# 3dofboard.net
KiCad netlist of a schematic drawn in EAGLE
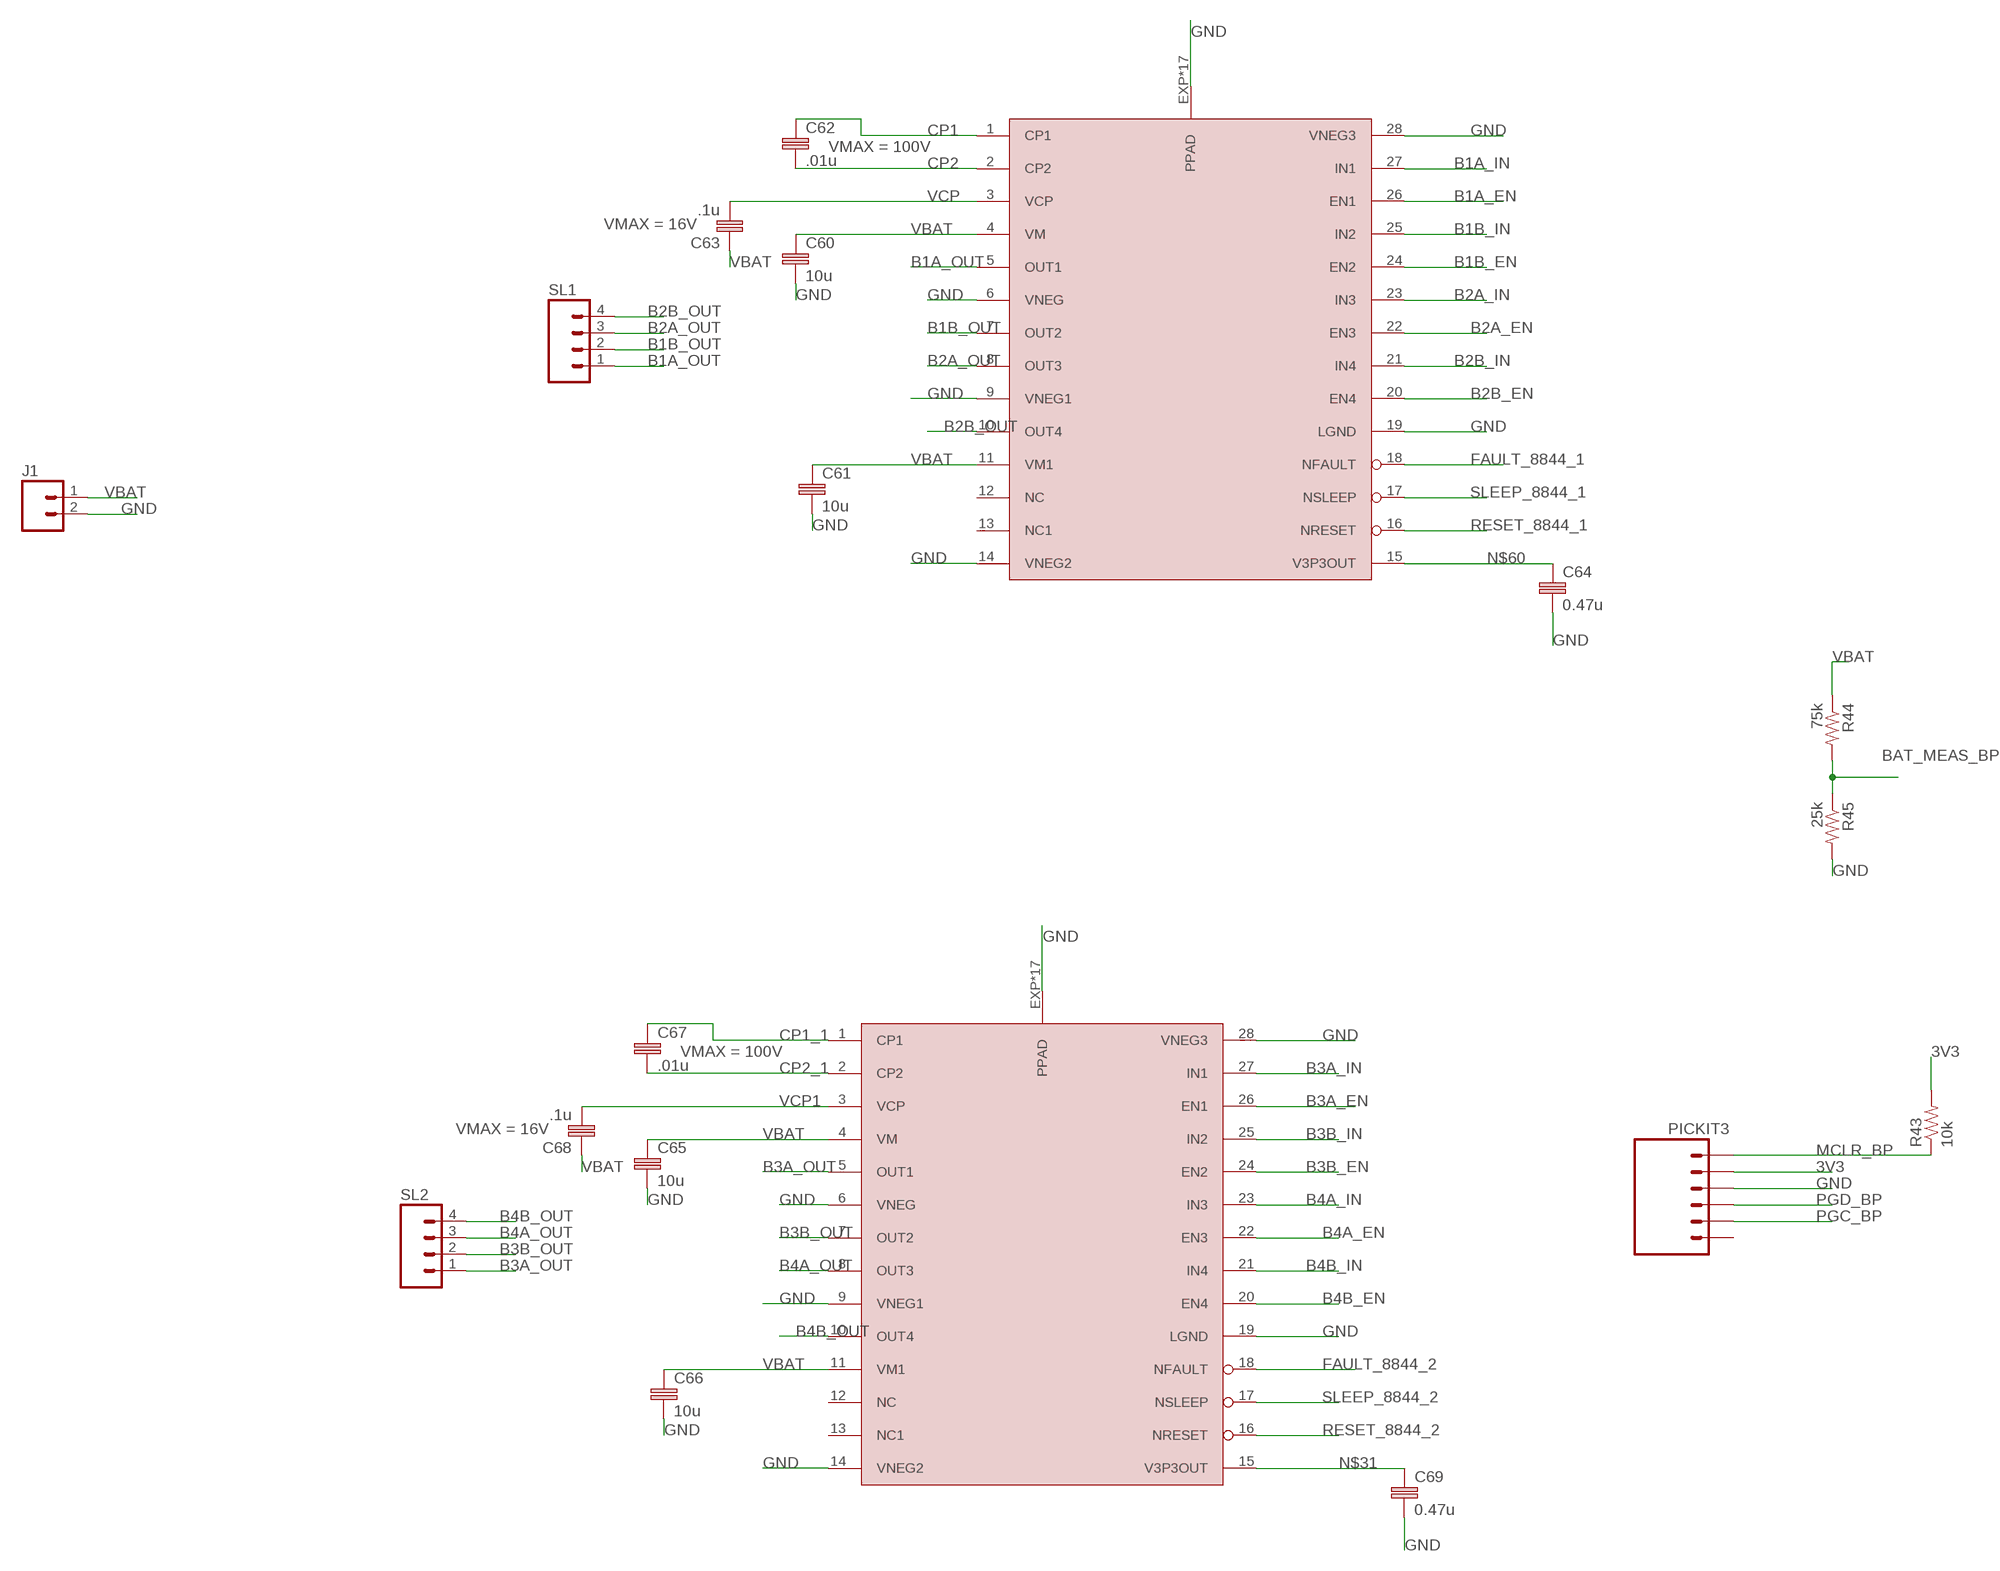
[diagram p0: schematic, sheet 1, part 1 of 3]
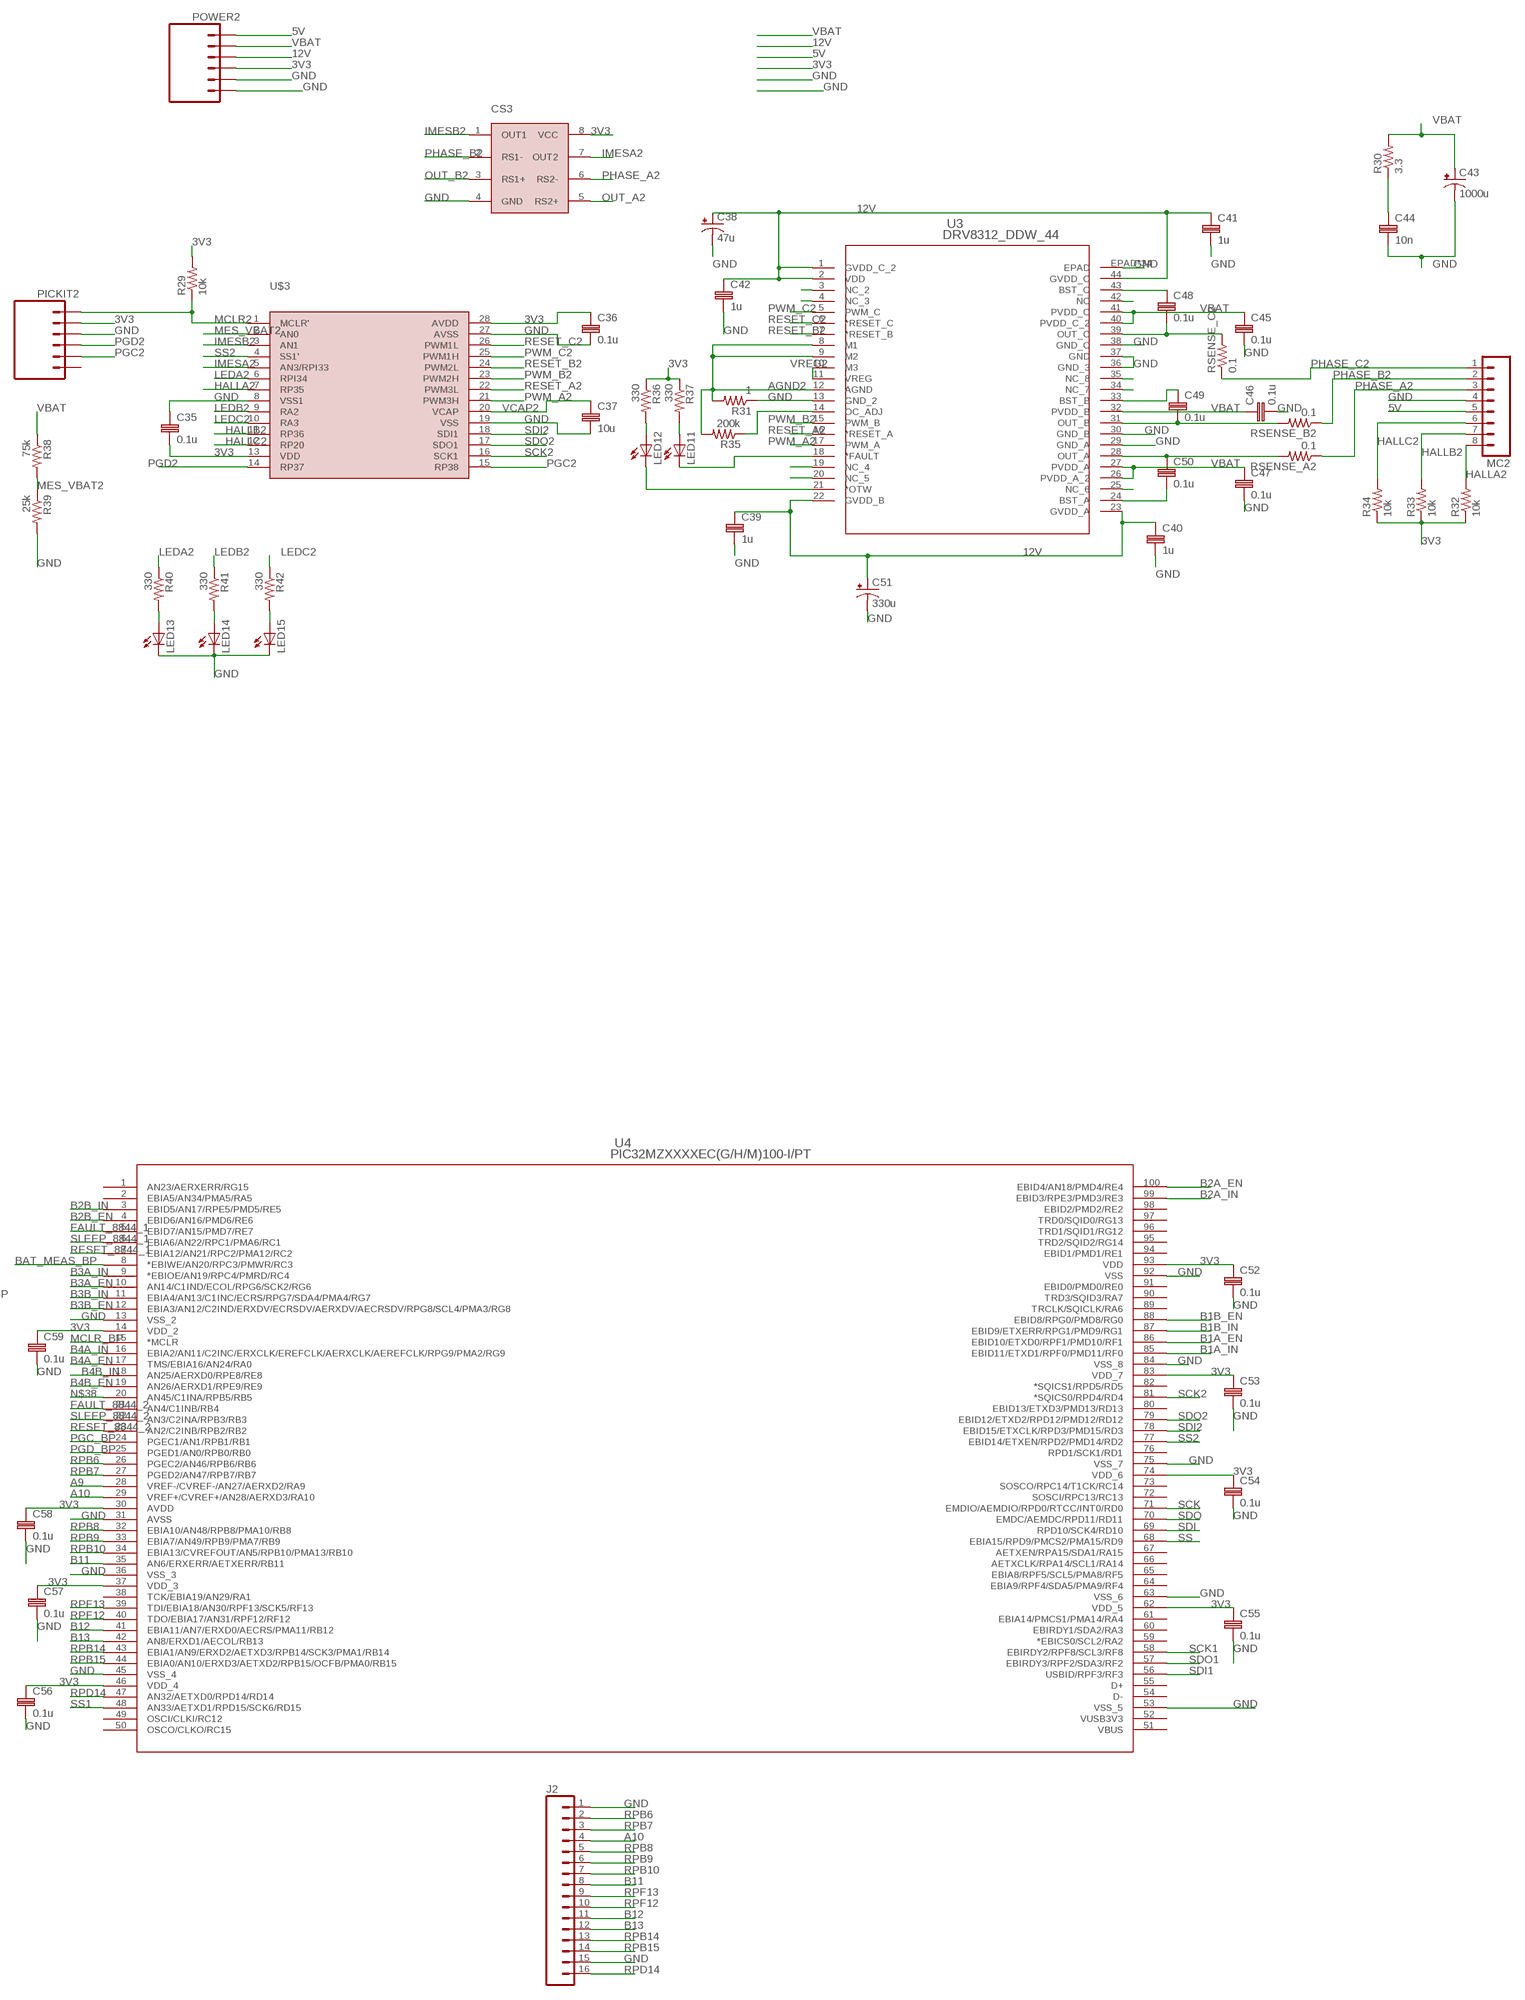
[diagram p1: schematic, sheet 1, part 2 of 3]
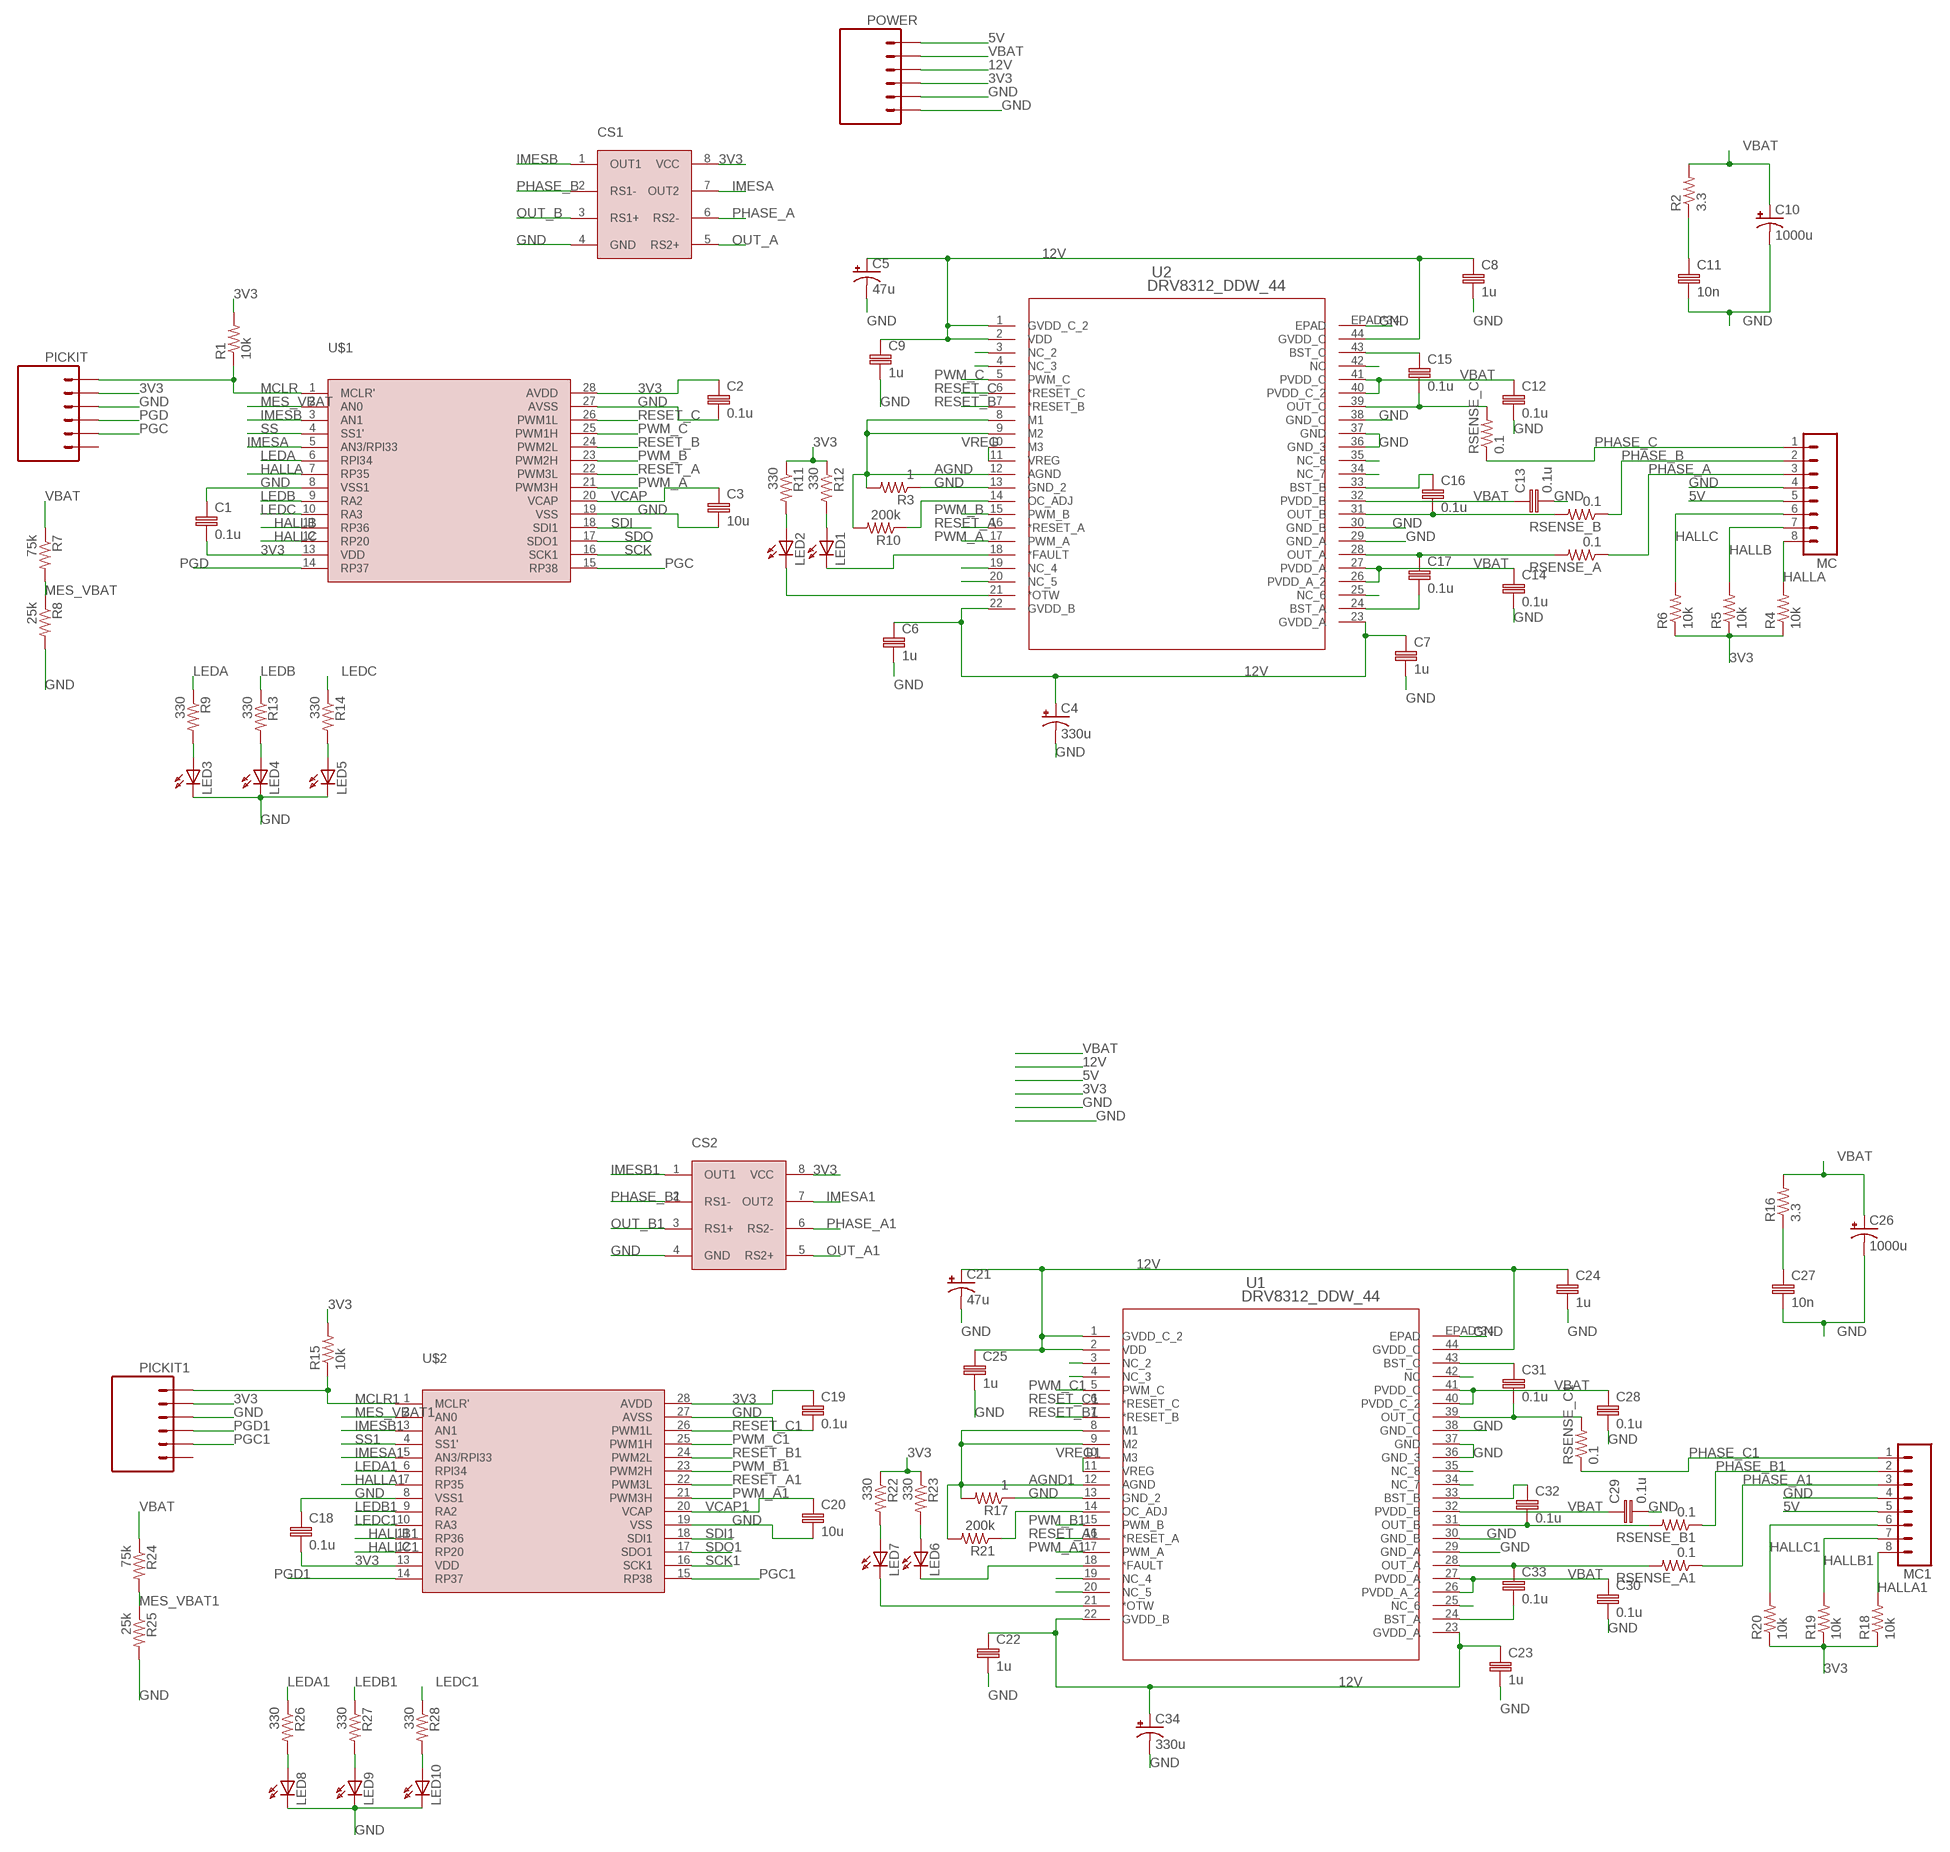
[diagram p2: schematic, sheet 1, part 3 of 3]

(export (version "E")
  (design (tool "Eeschema 10.0.6"))
  (components
    (comp (ref "C1")
      (value "0.1u")
      (footprint "eagle-import:0805")
      (libsource (lib "eagle-import") (part "CAP0805"))
    )
    (comp (ref "C2")
      (value "0.1u")
      (footprint "eagle-import:0805")
      (libsource (lib "eagle-import") (part "CAP0805"))
    )
    (comp (ref "C3")
      (value "10u")
      (footprint "eagle-import:0805")
      (libsource (lib "eagle-import") (part "CAP0805"))
    )
    (comp (ref "C4")
      (value "330u")
      (footprint "eagle-import:E3,5-8")
      (libsource (lib "eagle-import") (part "CPOL-USE3.5-8"))
    )
    (comp (ref "C5")
      (value "47u")
      (footprint "eagle-import:CPOL-RADIAL-100UF-25V")
      (libsource (lib "eagle-import") (part "CAP_POLPTH1"))
    )
    (comp (ref "C6")
      (value "1u")
      (footprint "eagle-import:0805")
      (libsource (lib "eagle-import") (part "CAP0805"))
    )
    (comp (ref "C7")
      (value "1u")
      (footprint "eagle-import:0805")
      (libsource (lib "eagle-import") (part "CAP0805"))
    )
    (comp (ref "C8")
      (value "1u")
      (footprint "eagle-import:0805")
      (libsource (lib "eagle-import") (part "CAP0805"))
    )
    (comp (ref "C9")
      (value "1u")
      (footprint "eagle-import:0805")
      (libsource (lib "eagle-import") (part "CAP0805"))
    )
    (comp (ref "C10")
      (value "1000u")
      (footprint "eagle-import:CPOL-RADIAL-1000UF-25V")
      (libsource (lib "eagle-import") (part "CAP_POLPTH4"))
    )
    (comp (ref "C11")
      (value "10n")
      (footprint "eagle-import:0805")
      (libsource (lib "eagle-import") (part "CAP0805"))
    )
    (comp (ref "C12")
      (value "0.1u")
      (footprint "eagle-import:0805")
      (libsource (lib "eagle-import") (part "CAP0805"))
    )
    (comp (ref "C13")
      (value "0.1u")
      (footprint "eagle-import:0805")
      (libsource (lib "eagle-import") (part "CAP0805"))
    )
    (comp (ref "C14")
      (value "0.1u")
      (footprint "eagle-import:0805")
      (libsource (lib "eagle-import") (part "CAP0805"))
    )
    (comp (ref "C15")
      (value "0.1u")
      (footprint "eagle-import:0805")
      (libsource (lib "eagle-import") (part "CAP0805"))
    )
    (comp (ref "C16")
      (value "0.1u")
      (footprint "eagle-import:0805")
      (libsource (lib "eagle-import") (part "CAP0805"))
    )
    (comp (ref "C17")
      (value "0.1u")
      (footprint "eagle-import:0805")
      (libsource (lib "eagle-import") (part "CAP0805"))
    )
    (comp (ref "C18")
      (value "0.1u")
      (footprint "eagle-import:0805")
      (libsource (lib "eagle-import") (part "CAP0805"))
    )
    (comp (ref "C19")
      (value "0.1u")
      (footprint "eagle-import:0805")
      (libsource (lib "eagle-import") (part "CAP0805"))
    )
    (comp (ref "C20")
      (value "10u")
      (footprint "eagle-import:0805")
      (libsource (lib "eagle-import") (part "CAP0805"))
    )
    (comp (ref "C21")
      (value "47u")
      (footprint "eagle-import:CPOL-RADIAL-100UF-25V")
      (libsource (lib "eagle-import") (part "CAP_POLPTH1"))
    )
    (comp (ref "C22")
      (value "1u")
      (footprint "eagle-import:0805")
      (libsource (lib "eagle-import") (part "CAP0805"))
    )
    (comp (ref "C23")
      (value "1u")
      (footprint "eagle-import:0805")
      (libsource (lib "eagle-import") (part "CAP0805"))
    )
    (comp (ref "C24")
      (value "1u")
      (footprint "eagle-import:0805")
      (libsource (lib "eagle-import") (part "CAP0805"))
    )
    (comp (ref "C25")
      (value "1u")
      (footprint "eagle-import:0805")
      (libsource (lib "eagle-import") (part "CAP0805"))
    )
    (comp (ref "C26")
      (value "1000u")
      (footprint "eagle-import:CPOL-RADIAL-1000UF-25V")
      (libsource (lib "eagle-import") (part "CAP_POLPTH4"))
    )
    (comp (ref "C27")
      (value "10n")
      (footprint "eagle-import:0805")
      (libsource (lib "eagle-import") (part "CAP0805"))
    )
    (comp (ref "C28")
      (value "0.1u")
      (footprint "eagle-import:0805")
      (libsource (lib "eagle-import") (part "CAP0805"))
    )
    (comp (ref "C29")
      (value "0.1u")
      (footprint "eagle-import:0805")
      (libsource (lib "eagle-import") (part "CAP0805"))
    )
    (comp (ref "C30")
      (value "0.1u")
      (footprint "eagle-import:0805")
      (libsource (lib "eagle-import") (part "CAP0805"))
    )
    (comp (ref "C31")
      (value "0.1u")
      (footprint "eagle-import:0805")
      (libsource (lib "eagle-import") (part "CAP0805"))
    )
    (comp (ref "C32")
      (value "0.1u")
      (footprint "eagle-import:0805")
      (libsource (lib "eagle-import") (part "CAP0805"))
    )
    (comp (ref "C33")
      (value "0.1u")
      (footprint "eagle-import:0805")
      (libsource (lib "eagle-import") (part "CAP0805"))
    )
    (comp (ref "C34")
      (value "330u")
      (footprint "eagle-import:E3,5-8")
      (libsource (lib "eagle-import") (part "CPOL-USE3.5-8"))
    )
    (comp (ref "C35")
      (value "0.1u")
      (footprint "eagle-import:0805")
      (libsource (lib "eagle-import") (part "CAP0805"))
    )
    (comp (ref "C36")
      (value "0.1u")
      (footprint "eagle-import:0805")
      (libsource (lib "eagle-import") (part "CAP0805"))
    )
    (comp (ref "C37")
      (value "10u")
      (footprint "eagle-import:0805")
      (libsource (lib "eagle-import") (part "CAP0805"))
    )
    (comp (ref "C38")
      (value "47u")
      (footprint "eagle-import:CPOL-RADIAL-100UF-25V")
      (libsource (lib "eagle-import") (part "CAP_POLPTH1"))
    )
    (comp (ref "C39")
      (value "1u")
      (footprint "eagle-import:0805")
      (libsource (lib "eagle-import") (part "CAP0805"))
    )
    (comp (ref "C40")
      (value "1u")
      (footprint "eagle-import:0805")
      (libsource (lib "eagle-import") (part "CAP0805"))
    )
    (comp (ref "C41")
      (value "1u")
      (footprint "eagle-import:0805")
      (libsource (lib "eagle-import") (part "CAP0805"))
    )
    (comp (ref "C42")
      (value "1u")
      (footprint "eagle-import:0805")
      (libsource (lib "eagle-import") (part "CAP0805"))
    )
    (comp (ref "C43")
      (value "1000u")
      (footprint "eagle-import:CPOL-RADIAL-1000UF-25V")
      (libsource (lib "eagle-import") (part "CAP_POLPTH4"))
    )
    (comp (ref "C44")
      (value "10n")
      (footprint "eagle-import:0805")
      (libsource (lib "eagle-import") (part "CAP0805"))
    )
    (comp (ref "C45")
      (value "0.1u")
      (footprint "eagle-import:0805")
      (libsource (lib "eagle-import") (part "CAP0805"))
    )
    (comp (ref "C46")
      (value "0.1u")
      (footprint "eagle-import:0805")
      (libsource (lib "eagle-import") (part "CAP0805"))
    )
    (comp (ref "C47")
      (value "0.1u")
      (footprint "eagle-import:0805")
      (libsource (lib "eagle-import") (part "CAP0805"))
    )
    (comp (ref "C48")
      (value "0.1u")
      (footprint "eagle-import:0805")
      (libsource (lib "eagle-import") (part "CAP0805"))
    )
    (comp (ref "C49")
      (value "0.1u")
      (footprint "eagle-import:0805")
      (libsource (lib "eagle-import") (part "CAP0805"))
    )
    (comp (ref "C50")
      (value "0.1u")
      (footprint "eagle-import:0805")
      (libsource (lib "eagle-import") (part "CAP0805"))
    )
    (comp (ref "C51")
      (value "330u")
      (footprint "eagle-import:E3,5-8")
      (libsource (lib "eagle-import") (part "CPOL-USE3.5-8"))
    )
    (comp (ref "C52")
      (value "0.1u")
      (footprint "eagle-import:0805")
      (libsource (lib "eagle-import") (part "CAP0805"))
    )
    (comp (ref "C53")
      (value "0.1u")
      (footprint "eagle-import:0805")
      (libsource (lib "eagle-import") (part "CAP0805"))
    )
    (comp (ref "C54")
      (value "0.1u")
      (footprint "eagle-import:0805")
      (libsource (lib "eagle-import") (part "CAP0805"))
    )
    (comp (ref "C55")
      (value "0.1u")
      (footprint "eagle-import:0805")
      (libsource (lib "eagle-import") (part "CAP0805"))
    )
    (comp (ref "C56")
      (value "0.1u")
      (footprint "eagle-import:0805")
      (libsource (lib "eagle-import") (part "CAP0805"))
    )
    (comp (ref "C57")
      (value "0.1u")
      (footprint "eagle-import:0805")
      (libsource (lib "eagle-import") (part "CAP0805"))
    )
    (comp (ref "C58")
      (value "0.1u")
      (footprint "eagle-import:0805")
      (libsource (lib "eagle-import") (part "CAP0805"))
    )
    (comp (ref "C59")
      (value "0.1u")
      (footprint "eagle-import:0805")
      (libsource (lib "eagle-import") (part "CAP0805"))
    )
    (comp (ref "C60")
      (value "10u")
      (footprint "eagle-import:0805")
      (libsource (lib "eagle-import") (part "CAP0805"))
    )
    (comp (ref "C61")
      (value "10u")
      (footprint "eagle-import:0805")
      (libsource (lib "eagle-import") (part "CAP0805"))
    )
    (comp (ref "C62")
      (value ".01u")
      (footprint "eagle-import:0805")
      (fields (field (name "VMAX") "100V"))
      (libsource (lib "eagle-import") (part "CAP0805"))
    )
    (comp (ref "C63")
      (value ".1u")
      (footprint "eagle-import:0805")
      (fields (field (name "VMAX") "16V"))
      (libsource (lib "eagle-import") (part "CAP0805"))
    )
    (comp (ref "C64")
      (value "0.47u")
      (footprint "eagle-import:0805")
      (libsource (lib "eagle-import") (part "CAP0805"))
    )
    (comp (ref "C65")
      (value "10u")
      (footprint "eagle-import:0805")
      (libsource (lib "eagle-import") (part "CAP0805"))
    )
    (comp (ref "C66")
      (value "10u")
      (footprint "eagle-import:0805")
      (libsource (lib "eagle-import") (part "CAP0805"))
    )
    (comp (ref "C67")
      (value ".01u")
      (footprint "eagle-import:0805")
      (fields (field (name "VMAX") "100V"))
      (libsource (lib "eagle-import") (part "CAP0805"))
    )
    (comp (ref "C68")
      (value ".1u")
      (footprint "eagle-import:0805")
      (fields (field (name "VMAX") "16V"))
      (libsource (lib "eagle-import") (part "CAP0805"))
    )
    (comp (ref "C69")
      (value "0.47u")
      (footprint "eagle-import:0805")
      (libsource (lib "eagle-import") (part "CAP0805"))
    )
    (comp (ref "CS1")
      (value "MAX4376")
      (footprint "eagle-import:SO8")
      (libsource (lib "eagle-import") (part "MAX4376"))
    )
    (comp (ref "CS2")
      (value "MAX4376")
      (footprint "eagle-import:SO8")
      (libsource (lib "eagle-import") (part "MAX4376"))
    )
    (comp (ref "CS3")
      (value "MAX4376")
      (footprint "eagle-import:SO8")
      (libsource (lib "eagle-import") (part "MAX4376"))
    )
    (comp (ref "J1")
      (value "M02LOCK")
      (footprint "eagle-import:1X02_LOCK")
      (libsource (lib "eagle-import") (part "M02LOCK"))
    )
    (comp (ref "J2")
      (value "M16DUAL_ROW")
      (footprint "eagle-import:2X8")
      (libsource (lib "eagle-import") (part "M16DUAL_ROW"))
    )
    (comp (ref "LED1")
      (value "LED0805")
      (footprint "eagle-import:LED-0805")
      (libsource (lib "eagle-import") (part "LED0805"))
    )
    (comp (ref "LED2")
      (value "LED0805")
      (footprint "eagle-import:LED-0805")
      (libsource (lib "eagle-import") (part "LED0805"))
    )
    (comp (ref "LED3")
      (value "LED0805")
      (footprint "eagle-import:LED-0805")
      (libsource (lib "eagle-import") (part "LED0805"))
    )
    (comp (ref "LED4")
      (value "LED0805")
      (footprint "eagle-import:LED-0805")
      (libsource (lib "eagle-import") (part "LED0805"))
    )
    (comp (ref "LED5")
      (value "LED0805")
      (footprint "eagle-import:LED-0805")
      (libsource (lib "eagle-import") (part "LED0805"))
    )
    (comp (ref "LED6")
      (value "LED0805")
      (footprint "eagle-import:LED-0805")
      (libsource (lib "eagle-import") (part "LED0805"))
    )
    (comp (ref "LED7")
      (value "LED0805")
      (footprint "eagle-import:LED-0805")
      (libsource (lib "eagle-import") (part "LED0805"))
    )
    (comp (ref "LED8")
      (value "LED0805")
      (footprint "eagle-import:LED-0805")
      (libsource (lib "eagle-import") (part "LED0805"))
    )
    (comp (ref "LED9")
      (value "LED0805")
      (footprint "eagle-import:LED-0805")
      (libsource (lib "eagle-import") (part "LED0805"))
    )
    (comp (ref "LED10")
      (value "LED0805")
      (footprint "eagle-import:LED-0805")
      (libsource (lib "eagle-import") (part "LED0805"))
    )
    (comp (ref "LED11")
      (value "LED0805")
      (footprint "eagle-import:LED-0805")
      (libsource (lib "eagle-import") (part "LED0805"))
    )
    (comp (ref "LED12")
      (value "LED0805")
      (footprint "eagle-import:LED-0805")
      (libsource (lib "eagle-import") (part "LED0805"))
    )
    (comp (ref "LED13")
      (value "LED0805")
      (footprint "eagle-import:LED-0805")
      (libsource (lib "eagle-import") (part "LED0805"))
    )
    (comp (ref "LED14")
      (value "LED0805")
      (footprint "eagle-import:LED-0805")
      (libsource (lib "eagle-import") (part "LED0805"))
    )
    (comp (ref "LED15")
      (value "LED0805")
      (footprint "eagle-import:LED-0805")
      (libsource (lib "eagle-import") (part "LED0805"))
    )
    (comp (ref "MC")
      (value "M08")
      (footprint "eagle-import:08P")
      (libsource (lib "eagle-import") (part "M08"))
    )
    (comp (ref "MC1")
      (value "M08")
      (footprint "eagle-import:08P")
      (libsource (lib "eagle-import") (part "M08"))
    )
    (comp (ref "MC2")
      (value "M08")
      (footprint "eagle-import:08P")
      (libsource (lib "eagle-import") (part "M08"))
    )
    (comp (ref "PICKIT")
      (value "M06LOCK")
      (footprint "eagle-import:1X06_LOCK")
      (libsource (lib "eagle-import") (part "M06LOCK"))
    )
    (comp (ref "PICKIT1")
      (value "M06LOCK")
      (footprint "eagle-import:1X06_LOCK")
      (libsource (lib "eagle-import") (part "M06LOCK"))
    )
    (comp (ref "PICKIT2")
      (value "M06LOCK")
      (footprint "eagle-import:1X06_LOCK")
      (libsource (lib "eagle-import") (part "M06LOCK"))
    )
    (comp (ref "PICKIT3")
      (value "M06LOCK")
      (footprint "eagle-import:1X06_LOCK")
      (libsource (lib "eagle-import") (part "M06LOCK"))
    )
    (comp (ref "POWER")
      (value "M06LOCK")
      (footprint "eagle-import:1X06_LOCK")
      (libsource (lib "eagle-import") (part "M06LOCK"))
    )
    (comp (ref "POWER2")
      (value "M06LOCK")
      (footprint "eagle-import:1X06_LOCK")
      (libsource (lib "eagle-import") (part "M06LOCK"))
    )
    (comp (ref "R1")
      (value "10k")
      (footprint "eagle-import:0805")
      (libsource (lib "eagle-import") (part "RESISTOR0805-RES"))
    )
    (comp (ref "R2")
      (value "3.3")
      (footprint "eagle-import:0805")
      (libsource (lib "eagle-import") (part "RESISTOR0805-RES"))
    )
    (comp (ref "R3")
      (value "1")
      (footprint "eagle-import:0805")
      (libsource (lib "eagle-import") (part "RESISTOR0805-RES"))
    )
    (comp (ref "R4")
      (value "10k")
      (footprint "eagle-import:0805")
      (libsource (lib "eagle-import") (part "RESISTOR0805-RES"))
    )
    (comp (ref "R5")
      (value "10k")
      (footprint "eagle-import:0805")
      (libsource (lib "eagle-import") (part "RESISTOR0805-RES"))
    )
    (comp (ref "R6")
      (value "10k")
      (footprint "eagle-import:0805")
      (libsource (lib "eagle-import") (part "RESISTOR0805-RES"))
    )
    (comp (ref "R7")
      (value "75k")
      (footprint "eagle-import:0805")
      (libsource (lib "eagle-import") (part "RESISTOR0805-RES"))
    )
    (comp (ref "R8")
      (value "25k")
      (footprint "eagle-import:0805")
      (libsource (lib "eagle-import") (part "RESISTOR0805-RES"))
    )
    (comp (ref "R9")
      (value "330")
      (footprint "eagle-import:0805")
      (libsource (lib "eagle-import") (part "RESISTOR0805-RES"))
    )
    (comp (ref "R10")
      (value "200k")
      (footprint "eagle-import:0805")
      (libsource (lib "eagle-import") (part "RESISTOR0805-RES"))
    )
    (comp (ref "R11")
      (value "330")
      (footprint "eagle-import:0805")
      (libsource (lib "eagle-import") (part "RESISTOR0805-RES"))
    )
    (comp (ref "R12")
      (value "330")
      (footprint "eagle-import:0805")
      (libsource (lib "eagle-import") (part "RESISTOR0805-RES"))
    )
    (comp (ref "R13")
      (value "330")
      (footprint "eagle-import:0805")
      (libsource (lib "eagle-import") (part "RESISTOR0805-RES"))
    )
    (comp (ref "R14")
      (value "330")
      (footprint "eagle-import:0805")
      (libsource (lib "eagle-import") (part "RESISTOR0805-RES"))
    )
    (comp (ref "R15")
      (value "10k")
      (footprint "eagle-import:0805")
      (libsource (lib "eagle-import") (part "RESISTOR0805-RES"))
    )
    (comp (ref "R16")
      (value "3.3")
      (footprint "eagle-import:0805")
      (libsource (lib "eagle-import") (part "RESISTOR0805-RES"))
    )
    (comp (ref "R17")
      (value "1")
      (footprint "eagle-import:0805")
      (libsource (lib "eagle-import") (part "RESISTOR0805-RES"))
    )
    (comp (ref "R18")
      (value "10k")
      (footprint "eagle-import:0805")
      (libsource (lib "eagle-import") (part "RESISTOR0805-RES"))
    )
    (comp (ref "R19")
      (value "10k")
      (footprint "eagle-import:0805")
      (libsource (lib "eagle-import") (part "RESISTOR0805-RES"))
    )
    (comp (ref "R20")
      (value "10k")
      (footprint "eagle-import:0805")
      (libsource (lib "eagle-import") (part "RESISTOR0805-RES"))
    )
    (comp (ref "R21")
      (value "200k")
      (footprint "eagle-import:0805")
      (libsource (lib "eagle-import") (part "RESISTOR0805-RES"))
    )
    (comp (ref "R22")
      (value "330")
      (footprint "eagle-import:0805")
      (libsource (lib "eagle-import") (part "RESISTOR0805-RES"))
    )
    (comp (ref "R23")
      (value "330")
      (footprint "eagle-import:0805")
      (libsource (lib "eagle-import") (part "RESISTOR0805-RES"))
    )
    (comp (ref "R24")
      (value "75k")
      (footprint "eagle-import:0805")
      (libsource (lib "eagle-import") (part "RESISTOR0805-RES"))
    )
    (comp (ref "R25")
      (value "25k")
      (footprint "eagle-import:0805")
      (libsource (lib "eagle-import") (part "RESISTOR0805-RES"))
    )
    (comp (ref "R26")
      (value "330")
      (footprint "eagle-import:0805")
      (libsource (lib "eagle-import") (part "RESISTOR0805-RES"))
    )
    (comp (ref "R27")
      (value "330")
      (footprint "eagle-import:0805")
      (libsource (lib "eagle-import") (part "RESISTOR0805-RES"))
    )
    (comp (ref "R28")
      (value "330")
      (footprint "eagle-import:0805")
      (libsource (lib "eagle-import") (part "RESISTOR0805-RES"))
    )
    (comp (ref "R29")
      (value "10k")
      (footprint "eagle-import:0805")
      (libsource (lib "eagle-import") (part "RESISTOR0805-RES"))
    )
    (comp (ref "R30")
      (value "3.3")
      (footprint "eagle-import:0805")
      (libsource (lib "eagle-import") (part "RESISTOR0805-RES"))
    )
    (comp (ref "R31")
      (value "1")
      (footprint "eagle-import:0805")
      (libsource (lib "eagle-import") (part "RESISTOR0805-RES"))
    )
    (comp (ref "R32")
      (value "10k")
      (footprint "eagle-import:0805")
      (libsource (lib "eagle-import") (part "RESISTOR0805-RES"))
    )
    (comp (ref "R33")
      (value "10k")
      (footprint "eagle-import:0805")
      (libsource (lib "eagle-import") (part "RESISTOR0805-RES"))
    )
    (comp (ref "R34")
      (value "10k")
      (footprint "eagle-import:0805")
      (libsource (lib "eagle-import") (part "RESISTOR0805-RES"))
    )
    (comp (ref "R35")
      (value "200k")
      (footprint "eagle-import:0805")
      (libsource (lib "eagle-import") (part "RESISTOR0805-RES"))
    )
    (comp (ref "R36")
      (value "330")
      (footprint "eagle-import:0805")
      (libsource (lib "eagle-import") (part "RESISTOR0805-RES"))
    )
    (comp (ref "R37")
      (value "330")
      (footprint "eagle-import:0805")
      (libsource (lib "eagle-import") (part "RESISTOR0805-RES"))
    )
    (comp (ref "R38")
      (value "75k")
      (footprint "eagle-import:0805")
      (libsource (lib "eagle-import") (part "RESISTOR0805-RES"))
    )
    (comp (ref "R39")
      (value "25k")
      (footprint "eagle-import:0805")
      (libsource (lib "eagle-import") (part "RESISTOR0805-RES"))
    )
    (comp (ref "R40")
      (value "330")
      (footprint "eagle-import:0805")
      (libsource (lib "eagle-import") (part "RESISTOR0805-RES"))
    )
    (comp (ref "R41")
      (value "330")
      (footprint "eagle-import:0805")
      (libsource (lib "eagle-import") (part "RESISTOR0805-RES"))
    )
    (comp (ref "R42")
      (value "330")
      (footprint "eagle-import:0805")
      (libsource (lib "eagle-import") (part "RESISTOR0805-RES"))
    )
    (comp (ref "R43")
      (value "10k")
      (footprint "eagle-import:0805")
      (libsource (lib "eagle-import") (part "RESISTOR0805-RES"))
    )
    (comp (ref "R44")
      (value "75k")
      (footprint "eagle-import:0805")
      (libsource (lib "eagle-import") (part "RESISTOR0805-RES"))
    )
    (comp (ref "R45")
      (value "25k")
      (footprint "eagle-import:0805")
      (libsource (lib "eagle-import") (part "RESISTOR0805-RES"))
    )
    (comp (ref "RSENSE_A")
      (value "0.1")
      (footprint "eagle-import:0805")
      (libsource (lib "eagle-import") (part "RESISTOR0805-RES"))
    )
    (comp (ref "RSENSE_A1")
      (value "0.1")
      (footprint "eagle-import:0805")
      (libsource (lib "eagle-import") (part "RESISTOR0805-RES"))
    )
    (comp (ref "RSENSE_A2")
      (value "0.1")
      (footprint "eagle-import:0805")
      (libsource (lib "eagle-import") (part "RESISTOR0805-RES"))
    )
    (comp (ref "RSENSE_B")
      (value "0.1")
      (footprint "eagle-import:0805")
      (libsource (lib "eagle-import") (part "RESISTOR0805-RES"))
    )
    (comp (ref "RSENSE_B1")
      (value "0.1")
      (footprint "eagle-import:0805")
      (libsource (lib "eagle-import") (part "RESISTOR0805-RES"))
    )
    (comp (ref "RSENSE_B2")
      (value "0.1")
      (footprint "eagle-import:0805")
      (libsource (lib "eagle-import") (part "RESISTOR0805-RES"))
    )
    (comp (ref "RSENSE_C")
      (value "0.1")
      (footprint "eagle-import:0805")
      (libsource (lib "eagle-import") (part "RESISTOR0805-RES"))
    )
    (comp (ref "RSENSE_C1")
      (value "0.1")
      (footprint "eagle-import:0805")
      (libsource (lib "eagle-import") (part "RESISTOR0805-RES"))
    )
    (comp (ref "RSENSE_C2")
      (value "0.1")
      (footprint "eagle-import:0805")
      (libsource (lib "eagle-import") (part "RESISTOR0805-RES"))
    )
    (comp (ref "SL1")
      (value "M04LOCK")
      (footprint "eagle-import:1X04_LOCK")
      (libsource (lib "eagle-import") (part "M04LOCK"))
    )
    (comp (ref "SL2")
      (value "M04LOCK")
      (footprint "eagle-import:1X04_LOCK")
      (libsource (lib "eagle-import") (part "M04LOCK"))
    )
    (comp (ref "U$1")
      (value "DSPIC33EP512MC502-28SSOP")
      (footprint "eagle-import:SSOP28")
      (libsource (lib "eagle-import") (part "DSPIC33EP512MC502-28SSOP"))
    )
    (comp (ref "U$2")
      (value "DSPIC33EP512MC502-28SSOP")
      (footprint "eagle-import:SSOP28")
      (libsource (lib "eagle-import") (part "DSPIC33EP512MC502-28SSOP"))
    )
    (comp (ref "U$3")
      (value "DSPIC33EP512MC502-28SSOP")
      (footprint "eagle-import:SSOP28")
      (libsource (lib "eagle-import") (part "DSPIC33EP512MC502-28SSOP"))
    )
    (comp (ref "U$4")
      (value "DRV8844PWP")
      (footprint "eagle-import:TSSOP-28")
      (libsource (lib "eagle-import") (part "DRV8844PWP"))
    )
    (comp (ref "U$5")
      (value "DRV8844PWP")
      (footprint "eagle-import:TSSOP-28")
      (libsource (lib "eagle-import") (part "DRV8844PWP"))
    )
    (comp (ref "U1")
      (value "DRV8312_DDW_44")
      (footprint "eagle-import:DDW44_8P26X4P31")
      (fields
        (field (name "GENERIC_PART_NUMBER") "DRV8312")
        (field (name "MANUFACTURER") "Texas Instruments")
        (field (name "MANUFACTURER_PART_NUMBER") "drv8312_ddw_44")
      )
      (libsource (lib "eagle-import") (part "DRV8312_DDW_44"))
    )
    (comp (ref "U2")
      (value "DRV8312_DDW_44")
      (footprint "eagle-import:DDW44_8P26X4P31")
      (fields
        (field (name "GENERIC_PART_NUMBER") "DRV8312")
        (field (name "MANUFACTURER") "Texas Instruments")
        (field (name "MANUFACTURER_PART_NUMBER") "drv8312_ddw_44")
      )
      (libsource (lib "eagle-import") (part "DRV8312_DDW_44"))
    )
    (comp (ref "U3")
      (value "DRV8312_DDW_44")
      (footprint "eagle-import:DDW44_8P26X4P31")
      (fields
        (field (name "GENERIC_PART_NUMBER") "DRV8312")
        (field (name "MANUFACTURER") "Texas Instruments")
        (field (name "MANUFACTURER_PART_NUMBER") "drv8312_ddw_44")
      )
      (libsource (lib "eagle-import") (part "DRV8312_DDW_44"))
    )
    (comp (ref "U4")
      (value "PIC32MZXXXXEC(G/H/M)100-I/PT")
      (footprint "eagle-import:TQFP100_12X12MC")
      (fields (field (name "MANUFACTURER_PART_NUMBER") "pic32mz1024ecg100-i/pt"))
      (libsource (lib "eagle-import") (part "PIC32MZXXXXEC(G/H/M)100-I/PT"))
    )
  )
  (nets
    (net (code "1") (name "/3V3") (class "Default")
      (node (ref "C1") (pin "2") (pinfunction "2_2") (pintype "passive"))
      (node (ref "C18") (pin "2") (pinfunction "2_2") (pintype "passive"))
      (node (ref "C19") (pin "1") (pinfunction "1_1") (pintype "passive"))
      (node (ref "C2") (pin "1") (pinfunction "1_1") (pintype "passive"))
      (node (ref "C35") (pin "2") (pinfunction "2_2") (pintype "passive"))
      (node (ref "C36") (pin "1") (pinfunction "1_1") (pintype "passive"))
      (node (ref "C52") (pin "1") (pinfunction "1_1") (pintype "passive"))
      (node (ref "C53") (pin "1") (pinfunction "1_1") (pintype "passive"))
      (node (ref "C54") (pin "1") (pinfunction "1_1") (pintype "passive"))
      (node (ref "C55") (pin "1") (pinfunction "1_1") (pintype "passive"))
      (node (ref "C56") (pin "1") (pinfunction "1_1") (pintype "passive"))
      (node (ref "C57") (pin "1") (pinfunction "1_1") (pintype "passive"))
      (node (ref "C58") (pin "1") (pinfunction "1_1") (pintype "passive"))
      (node (ref "C59") (pin "1") (pinfunction "1_1") (pintype "passive"))
      (node (ref "CS1") (pin "8") (pinfunction "VCC_8") (pintype "bidirectional"))
      (node (ref "CS2") (pin "8") (pinfunction "VCC_8") (pintype "bidirectional"))
      (node (ref "CS3") (pin "8") (pinfunction "VCC_8") (pintype "bidirectional"))
      (node (ref "PICKIT") (pin "2") (pinfunction "2_2") (pintype "passive"))
      (node (ref "PICKIT1") (pin "2") (pinfunction "2_2") (pintype "passive"))
      (node (ref "PICKIT2") (pin "2") (pinfunction "2_2") (pintype "passive"))
      (node (ref "PICKIT3") (pin "2") (pinfunction "2_2") (pintype "passive"))
      (node (ref "POWER") (pin "4") (pinfunction "4_4") (pintype "passive"))
      (node (ref "POWER2") (pin "4") (pinfunction "4_4") (pintype "passive"))
      (node (ref "R1") (pin "2") (pinfunction "2_2") (pintype "passive"))
      (node (ref "R11") (pin "1") (pinfunction "1_1") (pintype "passive"))
      (node (ref "R12") (pin "1") (pinfunction "1_1") (pintype "passive"))
      (node (ref "R15") (pin "2") (pinfunction "2_2") (pintype "passive"))
      (node (ref "R18") (pin "1") (pinfunction "1_1") (pintype "passive"))
      (node (ref "R19") (pin "1") (pinfunction "1_1") (pintype "passive"))
      (node (ref "R20") (pin "1") (pinfunction "1_1") (pintype "passive"))
      (node (ref "R22") (pin "1") (pinfunction "1_1") (pintype "passive"))
      (node (ref "R23") (pin "1") (pinfunction "1_1") (pintype "passive"))
      (node (ref "R29") (pin "2") (pinfunction "2_2") (pintype "passive"))
      (node (ref "R32") (pin "1") (pinfunction "1_1") (pintype "passive"))
      (node (ref "R33") (pin "1") (pinfunction "1_1") (pintype "passive"))
      (node (ref "R34") (pin "1") (pinfunction "1_1") (pintype "passive"))
      (node (ref "R36") (pin "1") (pinfunction "1_1") (pintype "passive"))
      (node (ref "R37") (pin "1") (pinfunction "1_1") (pintype "passive"))
      (node (ref "R4") (pin "1") (pinfunction "1_1") (pintype "passive"))
      (node (ref "R43") (pin "2") (pinfunction "2_2") (pintype "passive"))
      (node (ref "R5") (pin "1") (pinfunction "1_1") (pintype "passive"))
      (node (ref "R6") (pin "1") (pinfunction "1_1") (pintype "passive"))
      (node (ref "U$1") (pin "13") (pinfunction "VDD_13") (pintype "bidirectional"))
      (node (ref "U$1") (pin "28") (pinfunction "AVDD_28") (pintype "bidirectional"))
      (node (ref "U$2") (pin "13") (pinfunction "VDD_13") (pintype "bidirectional"))
      (node (ref "U$2") (pin "28") (pinfunction "AVDD_28") (pintype "bidirectional"))
      (node (ref "U$3") (pin "13") (pinfunction "VDD_13") (pintype "bidirectional"))
      (node (ref "U$3") (pin "28") (pinfunction "AVDD_28") (pintype "bidirectional"))
      (node (ref "U4") (pin "14") (pinfunction "VDD_2_14") (pintype "power_in"))
      (node (ref "U4") (pin "30") (pinfunction "AVDD_30") (pintype "power_in"))
      (node (ref "U4") (pin "37") (pinfunction "VDD_3_37") (pintype "power_in"))
      (node (ref "U4") (pin "46") (pinfunction "VDD_4_46") (pintype "power_in"))
      (node (ref "U4") (pin "62") (pinfunction "VDD_5_62") (pintype "power_in"))
      (node (ref "U4") (pin "74") (pinfunction "VDD_6_74") (pintype "power_in"))
      (node (ref "U4") (pin "83") (pinfunction "VDD_7_83") (pintype "power_in"))
      (node (ref "U4") (pin "93") (pinfunction "VDD_93") (pintype "power_in"))
    )
    (net (code "2") (name "/5V") (class "Default")
      (node (ref "MC") (pin "5") (pinfunction "5_5") (pintype "passive"))
      (node (ref "MC1") (pin "5") (pinfunction "5_5") (pintype "passive"))
      (node (ref "MC2") (pin "5") (pinfunction "5_5") (pintype "passive"))
      (node (ref "POWER") (pin "1") (pinfunction "1_1") (pintype "passive"))
      (node (ref "POWER2") (pin "1") (pinfunction "1_1") (pintype "passive"))
    )
    (net (code "3") (name "/12V") (class "Default")
      (node (ref "C21") (pin "1") (pinfunction "+_1") (pintype "passive"))
      (node (ref "C22") (pin "1") (pinfunction "1_1") (pintype "passive"))
      (node (ref "C23") (pin "1") (pinfunction "1_1") (pintype "passive"))
      (node (ref "C24") (pin "1") (pinfunction "1_1") (pintype "passive"))
      (node (ref "C25") (pin "1") (pinfunction "1_1") (pintype "passive"))
      (node (ref "C34") (pin "+") (pinfunction "+_+") (pintype "passive"))
      (node (ref "C38") (pin "1") (pinfunction "+_1") (pintype "passive"))
      (node (ref "C39") (pin "1") (pinfunction "1_1") (pintype "passive"))
      (node (ref "C4") (pin "+") (pinfunction "+_+") (pintype "passive"))
      (node (ref "C40") (pin "1") (pinfunction "1_1") (pintype "passive"))
      (node (ref "C41") (pin "1") (pinfunction "1_1") (pintype "passive"))
      (node (ref "C42") (pin "1") (pinfunction "1_1") (pintype "passive"))
      (node (ref "C5") (pin "1") (pinfunction "+_1") (pintype "passive"))
      (node (ref "C51") (pin "+") (pinfunction "+_+") (pintype "passive"))
      (node (ref "C6") (pin "1") (pinfunction "1_1") (pintype "passive"))
      (node (ref "C7") (pin "1") (pinfunction "1_1") (pintype "passive"))
      (node (ref "C8") (pin "1") (pinfunction "1_1") (pintype "passive"))
      (node (ref "C9") (pin "1") (pinfunction "1_1") (pintype "passive"))
      (node (ref "POWER") (pin "3") (pinfunction "3_3") (pintype "passive"))
      (node (ref "POWER2") (pin "3") (pinfunction "3_3") (pintype "passive"))
      (node (ref "U1") (pin "1") (pinfunction "GVDD_C_2_1") (pintype "power_in"))
      (node (ref "U1") (pin "2") (pinfunction "VDD_2") (pintype "power_in"))
      (node (ref "U1") (pin "22") (pinfunction "GVDD_B_22") (pintype "power_in"))
      (node (ref "U1") (pin "23") (pinfunction "GVDD_A_23") (pintype "power_in"))
      (node (ref "U1") (pin "44") (pinfunction "GVDD_C_44") (pintype "power_in"))
      (node (ref "U2") (pin "1") (pinfunction "GVDD_C_2_1") (pintype "power_in"))
      (node (ref "U2") (pin "2") (pinfunction "VDD_2") (pintype "power_in"))
      (node (ref "U2") (pin "22") (pinfunction "GVDD_B_22") (pintype "power_in"))
      (node (ref "U2") (pin "23") (pinfunction "GVDD_A_23") (pintype "power_in"))
      (node (ref "U2") (pin "44") (pinfunction "GVDD_C_44") (pintype "power_in"))
      (node (ref "U3") (pin "1") (pinfunction "GVDD_C_2_1") (pintype "power_in"))
      (node (ref "U3") (pin "2") (pinfunction "VDD_2") (pintype "power_in"))
      (node (ref "U3") (pin "22") (pinfunction "GVDD_B_22") (pintype "power_in"))
      (node (ref "U3") (pin "23") (pinfunction "GVDD_A_23") (pintype "power_in"))
      (node (ref "U3") (pin "44") (pinfunction "GVDD_C_44") (pintype "power_in"))
    )
    (net (code "4") (name "/A9") (class "Default")
      (node (ref "U4") (pin "28") (pinfunction "VREF-/CVREF-/AN27/AERXD2/RA9_28") (pintype "bidirectional"))
    )
    (net (code "5") (name "/A10") (class "Default")
      (node (ref "J2") (pin "4") (pinfunction "4_4") (pintype "passive"))
      (node (ref "U4") (pin "29") (pinfunction "VREF+/CVREF+/AN28/AERXD3/RA10_29") (pintype "bidirectional"))
    )
    (net (code "6") (name "/AGND") (class "Default")
      (node (ref "R10") (pin "2") (pinfunction "2_2") (pintype "passive"))
      (node (ref "R3") (pin "2") (pinfunction "2_2") (pintype "passive"))
      (node (ref "U2") (pin "12") (pinfunction "AGND_12") (pintype "power_in"))
      (node (ref "U2") (pin "8") (pinfunction "M1_8") (pintype "input"))
      (node (ref "U2") (pin "9") (pinfunction "M2_9") (pintype "input"))
    )
    (net (code "7") (name "/AGND1") (class "Default")
      (node (ref "R17") (pin "2") (pinfunction "2_2") (pintype "passive"))
      (node (ref "R21") (pin "2") (pinfunction "2_2") (pintype "passive"))
      (node (ref "U1") (pin "12") (pinfunction "AGND_12") (pintype "power_in"))
      (node (ref "U1") (pin "8") (pinfunction "M1_8") (pintype "input"))
      (node (ref "U1") (pin "9") (pinfunction "M2_9") (pintype "input"))
    )
    (net (code "8") (name "/AGND2") (class "Default")
      (node (ref "R31") (pin "2") (pinfunction "2_2") (pintype "passive"))
      (node (ref "R35") (pin "2") (pinfunction "2_2") (pintype "passive"))
      (node (ref "U3") (pin "12") (pinfunction "AGND_12") (pintype "power_in"))
      (node (ref "U3") (pin "8") (pinfunction "M1_8") (pintype "input"))
      (node (ref "U3") (pin "9") (pinfunction "M2_9") (pintype "input"))
    )
    (net (code "9") (name "/B1A_EN") (class "Default")
      (node (ref "U$4") (pin "26") (pinfunction "EN1_26") (pintype "bidirectional"))
      (node (ref "U4") (pin "86") (pinfunction "EBID10/ETXD0/RPF1/PMD10/RF1_86") (pintype "bidirectional"))
    )
    (net (code "10") (name "/B1A_IN") (class "Default")
      (node (ref "U$4") (pin "27") (pinfunction "IN1_27") (pintype "bidirectional"))
      (node (ref "U4") (pin "85") (pinfunction "EBID11/ETXD1/RPF0/PMD11/RF0_85") (pintype "bidirectional"))
    )
    (net (code "11") (name "/B1A_OUT") (class "Default")
      (node (ref "SL1") (pin "1") (pinfunction "1_1") (pintype "passive"))
      (node (ref "U$4") (pin "5") (pinfunction "OUT1_5") (pintype "bidirectional"))
    )
    (net (code "12") (name "/B1B_EN") (class "Default")
      (node (ref "U$4") (pin "24") (pinfunction "EN2_24") (pintype "bidirectional"))
      (node (ref "U4") (pin "88") (pinfunction "EBID8/RPG0/PMD8/RG0_88") (pintype "bidirectional"))
    )
    (net (code "13") (name "/B1B_IN") (class "Default")
      (node (ref "U$4") (pin "25") (pinfunction "IN2_25") (pintype "bidirectional"))
      (node (ref "U4") (pin "87") (pinfunction "EBID9/ETXERR/RPG1/PMD9/RG1_87") (pintype "bidirectional"))
    )
    (net (code "14") (name "/B1B_OUT") (class "Default")
      (node (ref "SL1") (pin "2") (pinfunction "2_2") (pintype "passive"))
      (node (ref "U$4") (pin "7") (pinfunction "OUT2_7") (pintype "bidirectional"))
    )
    (net (code "15") (name "/B2A_EN") (class "Default")
      (node (ref "U$4") (pin "22") (pinfunction "EN3_22") (pintype "bidirectional"))
      (node (ref "U4") (pin "100") (pinfunction "EBID4/AN18/PMD4/RE4_100") (pintype "bidirectional"))
    )
    (net (code "16") (name "/B2A_IN") (class "Default")
      (node (ref "U$4") (pin "23") (pinfunction "IN3_23") (pintype "bidirectional"))
      (node (ref "U4") (pin "99") (pinfunction "EBID3/RPE3/PMD3/RE3_99") (pintype "bidirectional"))
    )
    (net (code "17") (name "/B2A_OUT") (class "Default")
      (node (ref "SL1") (pin "3") (pinfunction "3_3") (pintype "passive"))
      (node (ref "U$4") (pin "8") (pinfunction "OUT3_8") (pintype "bidirectional"))
    )
    (net (code "18") (name "/B2B_EN") (class "Default")
      (node (ref "U$4") (pin "20") (pinfunction "EN4_20") (pintype "bidirectional"))
      (node (ref "U4") (pin "4") (pinfunction "EBID6/AN16/PMD6/RE6_4") (pintype "bidirectional"))
    )
    (net (code "19") (name "/B2B_IN") (class "Default")
      (node (ref "U$4") (pin "21") (pinfunction "IN4_21") (pintype "bidirectional"))
      (node (ref "U4") (pin "3") (pinfunction "EBID5/AN17/RPE5/PMD5/RE5_3") (pintype "bidirectional"))
    )
    (net (code "20") (name "/B2B_OUT") (class "Default")
      (node (ref "SL1") (pin "4") (pinfunction "4_4") (pintype "passive"))
      (node (ref "U$4") (pin "10") (pinfunction "OUT4_10") (pintype "bidirectional"))
    )
    (net (code "21") (name "/B3A_EN") (class "Default")
      (node (ref "U$5") (pin "26") (pinfunction "EN1_26") (pintype "bidirectional"))
      (node (ref "U4") (pin "10") (pinfunction "AN14/C1IND/ECOL/RPG6/SCK2/RG6_10") (pintype "bidirectional"))
    )
    (net (code "22") (name "/B3A_IN") (class "Default")
      (node (ref "U$5") (pin "27") (pinfunction "IN1_27") (pintype "bidirectional"))
      (node (ref "U4") (pin "9") (pinfunction "*EBIOE/AN19/RPC4/PMRD/RC4_9") (pintype "bidirectional"))
    )
    (net (code "23") (name "/B3A_OUT") (class "Default")
      (node (ref "SL2") (pin "1") (pinfunction "1_1") (pintype "passive"))
      (node (ref "U$5") (pin "5") (pinfunction "OUT1_5") (pintype "bidirectional"))
    )
    (net (code "24") (name "/B3B_EN") (class "Default")
      (node (ref "U$5") (pin "24") (pinfunction "EN2_24") (pintype "bidirectional"))
      (node (ref "U4") (pin "12") (pinfunction "EBIA3/AN12/C2IND/ERXDV/ECRSDV/AERXDV/AECRSDV/RPG8/SCL4/PMA3/RG8_12") (pintype "bidirectional"))
    )
    (net (code "25") (name "/B3B_IN") (class "Default")
      (node (ref "U$5") (pin "25") (pinfunction "IN2_25") (pintype "bidirectional"))
      (node (ref "U4") (pin "11") (pinfunction "EBIA4/AN13/C1INC/ECRS/RPG7/SDA4/PMA4/RG7_11") (pintype "bidirectional"))
    )
    (net (code "26") (name "/B3B_OUT") (class "Default")
      (node (ref "SL2") (pin "2") (pinfunction "2_2") (pintype "passive"))
      (node (ref "U$5") (pin "7") (pinfunction "OUT2_7") (pintype "bidirectional"))
    )
    (net (code "27") (name "/B4A_EN") (class "Default")
      (node (ref "U$5") (pin "22") (pinfunction "EN3_22") (pintype "bidirectional"))
      (node (ref "U4") (pin "17") (pinfunction "TMS/EBIA16/AN24/RA0_17") (pintype "bidirectional"))
    )
    (net (code "28") (name "/B4A_IN") (class "Default")
      (node (ref "U$5") (pin "23") (pinfunction "IN3_23") (pintype "bidirectional"))
      (node (ref "U4") (pin "16") (pinfunction "EBIA2/AN11/C2INC/ERXCLK/EREFCLK/AERXCLK/AEREFCLK/RPG9/PMA2/RG9_16") (pintype "bidirectional"))
    )
    (net (code "29") (name "/B4A_OUT") (class "Default")
      (node (ref "SL2") (pin "3") (pinfunction "3_3") (pintype "passive"))
      (node (ref "U$5") (pin "8") (pinfunction "OUT3_8") (pintype "bidirectional"))
    )
    (net (code "30") (name "/B4B_EN") (class "Default")
      (node (ref "U$5") (pin "20") (pinfunction "EN4_20") (pintype "bidirectional"))
      (node (ref "U4") (pin "19") (pinfunction "AN26/AERXD1/RPE9/RE9_19") (pintype "bidirectional"))
    )
    (net (code "31") (name "/B4B_IN") (class "Default")
      (node (ref "U$5") (pin "21") (pinfunction "IN4_21") (pintype "bidirectional"))
      (node (ref "U4") (pin "18") (pinfunction "AN25/AERXD0/RPE8/RE8_18") (pintype "bidirectional"))
    )
    (net (code "32") (name "/B4B_OUT") (class "Default")
      (node (ref "SL2") (pin "4") (pinfunction "4_4") (pintype "passive"))
      (node (ref "U$5") (pin "10") (pinfunction "OUT4_10") (pintype "bidirectional"))
    )
    (net (code "33") (name "/B11") (class "Default")
      (node (ref "J2") (pin "8") (pinfunction "8_8") (pintype "passive"))
      (node (ref "U4") (pin "35") (pinfunction "AN6/ERXERR/AETXERR/RB11_35") (pintype "bidirectional"))
    )
    (net (code "34") (name "/B12") (class "Default")
      (node (ref "J2") (pin "11") (pinfunction "11_11") (pintype "passive"))
      (node (ref "U4") (pin "41") (pinfunction "EBIA11/AN7/ERXD0/AECRS/PMA11/RB12_41") (pintype "bidirectional"))
    )
    (net (code "35") (name "/B13") (class "Default")
      (node (ref "J2") (pin "12") (pinfunction "12_12") (pintype "passive"))
      (node (ref "U4") (pin "42") (pinfunction "AN8/ERXD1/AECOL/RB13_42") (pintype "bidirectional"))
    )
    (net (code "36") (name "/BAT_MEAS_BP") (class "Default")
      (node (ref "R44") (pin "2") (pinfunction "2_2") (pintype "passive"))
      (node (ref "R45") (pin "1") (pinfunction "1_1") (pintype "passive"))
      (node (ref "U4") (pin "8") (pinfunction "*EBIWE/AN20/RPC3/PMWR/RC3_8") (pintype "bidirectional"))
    )
    (net (code "37") (name "/CP1") (class "Default")
      (node (ref "C62") (pin "1") (pinfunction "1_1") (pintype "passive"))
      (node (ref "U$4") (pin "1") (pinfunction "CP1_1") (pintype "bidirectional"))
    )
    (net (code "38") (name "/CP1_1") (class "Default")
      (node (ref "C67") (pin "1") (pinfunction "1_1") (pintype "passive"))
      (node (ref "U$5") (pin "1") (pinfunction "CP1_1") (pintype "bidirectional"))
    )
    (net (code "39") (name "/CP2") (class "Default")
      (node (ref "C62") (pin "2") (pinfunction "2_2") (pintype "passive"))
      (node (ref "U$4") (pin "2") (pinfunction "CP2_2") (pintype "bidirectional"))
    )
    (net (code "40") (name "/CP2_1") (class "Default")
      (node (ref "C67") (pin "2") (pinfunction "2_2") (pintype "passive"))
      (node (ref "U$5") (pin "2") (pinfunction "CP2_2") (pintype "bidirectional"))
    )
    (net (code "41") (name "/FAULT_8844_1") (class "Default")
      (node (ref "U$4") (pin "18") (pinfunction "NFAULT_18") (pintype "bidirectional"))
      (node (ref "U4") (pin "5") (pinfunction "EBID7/AN15/PMD7/RE7_5") (pintype "bidirectional"))
    )
    (net (code "42") (name "/FAULT_8844_2") (class "Default")
      (node (ref "U$5") (pin "18") (pinfunction "NFAULT_18") (pintype "bidirectional"))
      (node (ref "U4") (pin "21") (pinfunction "AN4/C1INB/RB4_21") (pintype "bidirectional"))
    )
    (net (code "43") (name "/GND") (class "Default")
      (node (ref "C1") (pin "1") (pinfunction "1_1") (pintype "passive"))
      (node (ref "C10") (pin "2") (pinfunction "-_2") (pintype "passive"))
      (node (ref "C11") (pin "2") (pinfunction "2_2") (pintype "passive"))
      (node (ref "C12") (pin "2") (pinfunction "2_2") (pintype "passive"))
      (node (ref "C13") (pin "2") (pinfunction "2_2") (pintype "passive"))
      (node (ref "C14") (pin "2") (pinfunction "2_2") (pintype "passive"))
      (node (ref "C18") (pin "1") (pinfunction "1_1") (pintype "passive"))
      (node (ref "C19") (pin "2") (pinfunction "2_2") (pintype "passive"))
      (node (ref "C2") (pin "2") (pinfunction "2_2") (pintype "passive"))
      (node (ref "C20") (pin "2") (pinfunction "2_2") (pintype "passive"))
      (node (ref "C21") (pin "2") (pinfunction "-_2") (pintype "passive"))
      (node (ref "C22") (pin "2") (pinfunction "2_2") (pintype "passive"))
      (node (ref "C23") (pin "2") (pinfunction "2_2") (pintype "passive"))
      (node (ref "C24") (pin "2") (pinfunction "2_2") (pintype "passive"))
      (node (ref "C25") (pin "2") (pinfunction "2_2") (pintype "passive"))
      (node (ref "C26") (pin "2") (pinfunction "-_2") (pintype "passive"))
      (node (ref "C27") (pin "2") (pinfunction "2_2") (pintype "passive"))
      (node (ref "C28") (pin "2") (pinfunction "2_2") (pintype "passive"))
      (node (ref "C29") (pin "2") (pinfunction "2_2") (pintype "passive"))
      (node (ref "C3") (pin "2") (pinfunction "2_2") (pintype "passive"))
      (node (ref "C30") (pin "2") (pinfunction "2_2") (pintype "passive"))
      (node (ref "C34") (pin "-") (pinfunction "-_-") (pintype "passive"))
      (node (ref "C35") (pin "1") (pinfunction "1_1") (pintype "passive"))
      (node (ref "C36") (pin "2") (pinfunction "2_2") (pintype "passive"))
      (node (ref "C37") (pin "2") (pinfunction "2_2") (pintype "passive"))
      (node (ref "C38") (pin "2") (pinfunction "-_2") (pintype "passive"))
      (node (ref "C39") (pin "2") (pinfunction "2_2") (pintype "passive"))
      (node (ref "C4") (pin "-") (pinfunction "-_-") (pintype "passive"))
      (node (ref "C40") (pin "2") (pinfunction "2_2") (pintype "passive"))
      (node (ref "C41") (pin "2") (pinfunction "2_2") (pintype "passive"))
      (node (ref "C42") (pin "2") (pinfunction "2_2") (pintype "passive"))
      (node (ref "C43") (pin "2") (pinfunction "-_2") (pintype "passive"))
      (node (ref "C44") (pin "2") (pinfunction "2_2") (pintype "passive"))
      (node (ref "C45") (pin "2") (pinfunction "2_2") (pintype "passive"))
      (node (ref "C46") (pin "2") (pinfunction "2_2") (pintype "passive"))
      (node (ref "C47") (pin "2") (pinfunction "2_2") (pintype "passive"))
      (node (ref "C5") (pin "2") (pinfunction "-_2") (pintype "passive"))
      (node (ref "C51") (pin "-") (pinfunction "-_-") (pintype "passive"))
      (node (ref "C52") (pin "2") (pinfunction "2_2") (pintype "passive"))
      (node (ref "C53") (pin "2") (pinfunction "2_2") (pintype "passive"))
      (node (ref "C54") (pin "2") (pinfunction "2_2") (pintype "passive"))
      (node (ref "C55") (pin "2") (pinfunction "2_2") (pintype "passive"))
      (node (ref "C56") (pin "2") (pinfunction "2_2") (pintype "passive"))
      (node (ref "C57") (pin "2") (pinfunction "2_2") (pintype "passive"))
      (node (ref "C58") (pin "2") (pinfunction "2_2") (pintype "passive"))
      (node (ref "C59") (pin "2") (pinfunction "2_2") (pintype "passive"))
      (node (ref "C6") (pin "2") (pinfunction "2_2") (pintype "passive"))
      (node (ref "C60") (pin "2") (pinfunction "2_2") (pintype "passive"))
      (node (ref "C61") (pin "2") (pinfunction "2_2") (pintype "passive"))
      (node (ref "C64") (pin "2") (pinfunction "2_2") (pintype "passive"))
      (node (ref "C65") (pin "2") (pinfunction "2_2") (pintype "passive"))
      (node (ref "C66") (pin "2") (pinfunction "2_2") (pintype "passive"))
      (node (ref "C69") (pin "2") (pinfunction "2_2") (pintype "passive"))
      (node (ref "C7") (pin "2") (pinfunction "2_2") (pintype "passive"))
      (node (ref "C8") (pin "2") (pinfunction "2_2") (pintype "passive"))
      (node (ref "C9") (pin "2") (pinfunction "2_2") (pintype "passive"))
      (node (ref "CS1") (pin "4") (pinfunction "GND_4") (pintype "bidirectional"))
      (node (ref "CS2") (pin "4") (pinfunction "GND_4") (pintype "bidirectional"))
      (node (ref "CS3") (pin "4") (pinfunction "GND_4") (pintype "bidirectional"))
      (node (ref "J1") (pin "2") (pinfunction "1_2") (pintype "passive"))
      (node (ref "J2") (pin "1") (pinfunction "1_1") (pintype "passive"))
      (node (ref "J2") (pin "15") (pinfunction "15_15") (pintype "passive"))
      (node (ref "LED10") (pin "2") (pinfunction "C_2") (pintype "passive"))
      (node (ref "LED13") (pin "2") (pinfunction "C_2") (pintype "passive"))
      (node (ref "LED14") (pin "2") (pinfunction "C_2") (pintype "passive"))
      (node (ref "LED15") (pin "2") (pinfunction "C_2") (pintype "passive"))
      (node (ref "LED3") (pin "2") (pinfunction "C_2") (pintype "passive"))
      (node (ref "LED4") (pin "2") (pinfunction "C_2") (pintype "passive"))
      (node (ref "LED5") (pin "2") (pinfunction "C_2") (pintype "passive"))
      (node (ref "LED8") (pin "2") (pinfunction "C_2") (pintype "passive"))
      (node (ref "LED9") (pin "2") (pinfunction "C_2") (pintype "passive"))
      (node (ref "MC") (pin "4") (pinfunction "4_4") (pintype "passive"))
      (node (ref "MC1") (pin "4") (pinfunction "4_4") (pintype "passive"))
      (node (ref "MC2") (pin "4") (pinfunction "4_4") (pintype "passive"))
      (node (ref "PICKIT") (pin "3") (pinfunction "3_3") (pintype "passive"))
      (node (ref "PICKIT1") (pin "3") (pinfunction "3_3") (pintype "passive"))
      (node (ref "PICKIT2") (pin "3") (pinfunction "3_3") (pintype "passive"))
      (node (ref "PICKIT3") (pin "3") (pinfunction "3_3") (pintype "passive"))
      (node (ref "POWER") (pin "5") (pinfunction "5_5") (pintype "passive"))
      (node (ref "POWER") (pin "6") (pinfunction "6_6") (pintype "passive"))
      (node (ref "POWER2") (pin "5") (pinfunction "5_5") (pintype "passive"))
      (node (ref "POWER2") (pin "6") (pinfunction "6_6") (pintype "passive"))
      (node (ref "R17") (pin "1") (pinfunction "1_1") (pintype "passive"))
      (node (ref "R25") (pin "2") (pinfunction "2_2") (pintype "passive"))
      (node (ref "R3") (pin "1") (pinfunction "1_1") (pintype "passive"))
      (node (ref "R31") (pin "1") (pinfunction "1_1") (pintype "passive"))
      (node (ref "R39") (pin "2") (pinfunction "2_2") (pintype "passive"))
      (node (ref "R45") (pin "2") (pinfunction "2_2") (pintype "passive"))
      (node (ref "R8") (pin "2") (pinfunction "2_2") (pintype "passive"))
      (node (ref "U$1") (pin "19") (pinfunction "VSS_19") (pintype "bidirectional"))
      (node (ref "U$1") (pin "27") (pinfunction "AVSS_27") (pintype "bidirectional"))
      (node (ref "U$1") (pin "8") (pinfunction "VSS1_8") (pintype "bidirectional"))
      (node (ref "U$2") (pin "19") (pinfunction "VSS_19") (pintype "bidirectional"))
      (node (ref "U$2") (pin "27") (pinfunction "AVSS_27") (pintype "bidirectional"))
      (node (ref "U$2") (pin "8") (pinfunction "VSS1_8") (pintype "bidirectional"))
      (node (ref "U$3") (pin "19") (pinfunction "VSS_19") (pintype "bidirectional"))
      (node (ref "U$3") (pin "27") (pinfunction "AVSS_27") (pintype "bidirectional"))
      (node (ref "U$3") (pin "8") (pinfunction "VSS1_8") (pintype "bidirectional"))
      (node (ref "U$4") (pin "14") (pinfunction "VNEG2_14") (pintype "bidirectional"))
      (node (ref "U$4") (pin "19") (pinfunction "LGND_19") (pintype "bidirectional"))
      (node (ref "U$4") (pin "28") (pinfunction "VNEG3_28") (pintype "bidirectional"))
      (node (ref "U$4") (pin "6") (pinfunction "VNEG_6") (pintype "bidirectional"))
      (node (ref "U$4") (pin "9") (pinfunction "VNEG1_9") (pintype "bidirectional"))
      (node (ref "U$4") (pin "EXP") (pinfunction "PPAD_EXP") (pintype "bidirectional"))
      (node (ref "U$4") (pin "P$1") (pinfunction "PPAD_P$1") (pintype "bidirectional"))
      (node (ref "U$4") (pin "P$10") (pinfunction "PPAD_P$10") (pintype "bidirectional"))
      (node (ref "U$4") (pin "P$11") (pinfunction "PPAD_P$11") (pintype "bidirectional"))
      (node (ref "U$4") (pin "P$12") (pinfunction "PPAD_P$12") (pintype "bidirectional"))
      (node (ref "U$4") (pin "P$13") (pinfunction "PPAD_P$13") (pintype "bidirectional"))
      (node (ref "U$4") (pin "P$14") (pinfunction "PPAD_P$14") (pintype "bidirectional"))
      (node (ref "U$4") (pin "P$15") (pinfunction "PPAD_P$15") (pintype "bidirectional"))
      (node (ref "U$4") (pin "P$16") (pinfunction "PPAD_P$16") (pintype "bidirectional"))
      (node (ref "U$4") (pin "P$2") (pinfunction "PPAD_P$2") (pintype "bidirectional"))
      (node (ref "U$4") (pin "P$3") (pinfunction "PPAD_P$3") (pintype "bidirectional"))
      (node (ref "U$4") (pin "P$4") (pinfunction "PPAD_P$4") (pintype "bidirectional"))
      (node (ref "U$4") (pin "P$5") (pinfunction "PPAD_P$5") (pintype "bidirectional"))
      (node (ref "U$4") (pin "P$6") (pinfunction "PPAD_P$6") (pintype "bidirectional"))
      (node (ref "U$4") (pin "P$7") (pinfunction "PPAD_P$7") (pintype "bidirectional"))
      (node (ref "U$4") (pin "P$8") (pinfunction "PPAD_P$8") (pintype "bidirectional"))
      (node (ref "U$4") (pin "P$9") (pinfunction "PPAD_P$9") (pintype "bidirectional"))
      (node (ref "U$5") (pin "14") (pinfunction "VNEG2_14") (pintype "bidirectional"))
      (node (ref "U$5") (pin "19") (pinfunction "LGND_19") (pintype "bidirectional"))
      (node (ref "U$5") (pin "28") (pinfunction "VNEG3_28") (pintype "bidirectional"))
      (node (ref "U$5") (pin "6") (pinfunction "VNEG_6") (pintype "bidirectional"))
      (node (ref "U$5") (pin "9") (pinfunction "VNEG1_9") (pintype "bidirectional"))
      (node (ref "U$5") (pin "EXP") (pinfunction "PPAD_EXP") (pintype "bidirectional"))
      (node (ref "U$5") (pin "P$1") (pinfunction "PPAD_P$1") (pintype "bidirectional"))
      (node (ref "U$5") (pin "P$10") (pinfunction "PPAD_P$10") (pintype "bidirectional"))
      (node (ref "U$5") (pin "P$11") (pinfunction "PPAD_P$11") (pintype "bidirectional"))
      (node (ref "U$5") (pin "P$12") (pinfunction "PPAD_P$12") (pintype "bidirectional"))
      (node (ref "U$5") (pin "P$13") (pinfunction "PPAD_P$13") (pintype "bidirectional"))
      (node (ref "U$5") (pin "P$14") (pinfunction "PPAD_P$14") (pintype "bidirectional"))
      (node (ref "U$5") (pin "P$15") (pinfunction "PPAD_P$15") (pintype "bidirectional"))
      (node (ref "U$5") (pin "P$16") (pinfunction "PPAD_P$16") (pintype "bidirectional"))
      (node (ref "U$5") (pin "P$2") (pinfunction "PPAD_P$2") (pintype "bidirectional"))
      (node (ref "U$5") (pin "P$3") (pinfunction "PPAD_P$3") (pintype "bidirectional"))
      (node (ref "U$5") (pin "P$4") (pinfunction "PPAD_P$4") (pintype "bidirectional"))
      (node (ref "U$5") (pin "P$5") (pinfunction "PPAD_P$5") (pintype "bidirectional"))
      (node (ref "U$5") (pin "P$6") (pinfunction "PPAD_P$6") (pintype "bidirectional"))
      (node (ref "U$5") (pin "P$7") (pinfunction "PPAD_P$7") (pintype "bidirectional"))
      (node (ref "U$5") (pin "P$8") (pinfunction "PPAD_P$8") (pintype "bidirectional"))
      (node (ref "U$5") (pin "P$9") (pinfunction "PPAD_P$9") (pintype "bidirectional"))
      (node (ref "U1") (pin "13") (pinfunction "GND_2_13") (pintype "power_in"))
      (node (ref "U1") (pin "19") (pinfunction "NC_4_19") (pintype "passive"))
      (node (ref "U1") (pin "20") (pinfunction "NC_5_20") (pintype "passive"))
      (node (ref "U1") (pin "25") (pinfunction "NC_6_25") (pintype "passive"))
      (node (ref "U1") (pin "29") (pinfunction "GND_A_29") (pintype "power_in"))
      (node (ref "U1") (pin "3") (pinfunction "NC_2_3") (pintype "passive"))
      (node (ref "U1") (pin "30") (pinfunction "GND_B_30") (pintype "power_in"))
      (node (ref "U1") (pin "34") (pinfunction "NC_7_34") (pintype "passive"))
      (node (ref "U1") (pin "35") (pinfunction "NC_8_35") (pintype "passive"))
      (node (ref "U1") (pin "36") (pinfunction "GND_3_36") (pintype "power_in"))
      (node (ref "U1") (pin "37") (pinfunction "GND_37") (pintype "power_in"))
      (node (ref "U1") (pin "38") (pinfunction "GND_C_38") (pintype "power_in"))
      (node (ref "U1") (pin "4") (pinfunction "NC_3_4") (pintype "passive"))
      (node (ref "U1") (pin "42") (pinfunction "NC_42") (pintype "passive"))
      (node (ref "U1") (pin "EPAD") (pinfunction "EPAD_EPAD") (pintype "passive"))
      (node (ref "U1") (pin "P$1") (pinfunction "EPAD_P$1") (pintype "passive"))
      (node (ref "U1") (pin "P$10") (pinfunction "EPAD_P$10") (pintype "passive"))
      (node (ref "U1") (pin "P$11") (pinfunction "EPAD_P$11") (pintype "passive"))
      (node (ref "U1") (pin "P$12") (pinfunction "EPAD_P$12") (pintype "passive"))
      (node (ref "U1") (pin "P$13") (pinfunction "EPAD_P$13") (pintype "passive"))
      (node (ref "U1") (pin "P$14") (pinfunction "EPAD_P$14") (pintype "passive"))
      (node (ref "U1") (pin "P$15") (pinfunction "EPAD_P$15") (pintype "passive"))
      (node (ref "U1") (pin "P$16") (pinfunction "EPAD_P$16") (pintype "passive"))
      (node (ref "U1") (pin "P$17") (pinfunction "EPAD_P$17") (pintype "passive"))
      (node (ref "U1") (pin "P$18") (pinfunction "EPAD_P$18") (pintype "passive"))
      (node (ref "U1") (pin "P$19") (pinfunction "EPAD_P$19") (pintype "passive"))
      (node (ref "U1") (pin "P$2") (pinfunction "EPAD_P$2") (pintype "passive"))
      (node (ref "U1") (pin "P$20") (pinfunction "EPAD_P$20") (pintype "passive"))
      (node (ref "U1") (pin "P$21") (pinfunction "EPAD_P$21") (pintype "passive"))
      (node (ref "U1") (pin "P$22") (pinfunction "EPAD_P$22") (pintype "passive"))
      (node (ref "U1") (pin "P$23") (pinfunction "EPAD_P$23") (pintype "passive"))
      (node (ref "U1") (pin "P$24") (pinfunction "EPAD_P$24") (pintype "passive"))
      (node (ref "U1") (pin "P$25") (pinfunction "EPAD_P$25") (pintype "passive"))
      (node (ref "U1") (pin "P$26") (pinfunction "EPAD_P$26") (pintype "passive"))
      (node (ref "U1") (pin "P$27") (pinfunction "EPAD_P$27") (pintype "passive"))
      (node (ref "U1") (pin "P$28") (pinfunction "EPAD_P$28") (pintype "passive"))
      (node (ref "U1") (pin "P$29") (pinfunction "EPAD_P$29") (pintype "passive"))
      (node (ref "U1") (pin "P$3") (pinfunction "EPAD_P$3") (pintype "passive"))
      (node (ref "U1") (pin "P$30") (pinfunction "EPAD_P$30") (pintype "passive"))
      (node (ref "U1") (pin "P$31") (pinfunction "EPAD_P$31") (pintype "passive"))
      (node (ref "U1") (pin "P$32") (pinfunction "EPAD_P$32") (pintype "passive"))
      (node (ref "U1") (pin "P$33") (pinfunction "EPAD_P$33") (pintype "passive"))
      (node (ref "U1") (pin "P$4") (pinfunction "EPAD_P$4") (pintype "passive"))
      (node (ref "U1") (pin "P$5") (pinfunction "EPAD_P$5") (pintype "passive"))
      (node (ref "U1") (pin "P$6") (pinfunction "EPAD_P$6") (pintype "passive"))
      (node (ref "U1") (pin "P$7") (pinfunction "EPAD_P$7") (pintype "passive"))
      (node (ref "U1") (pin "P$8") (pinfunction "EPAD_P$8") (pintype "passive"))
      (node (ref "U1") (pin "P$9") (pinfunction "EPAD_P$9") (pintype "passive"))
      (node (ref "U2") (pin "13") (pinfunction "GND_2_13") (pintype "power_in"))
      (node (ref "U2") (pin "19") (pinfunction "NC_4_19") (pintype "passive"))
      (node (ref "U2") (pin "20") (pinfunction "NC_5_20") (pintype "passive"))
      (node (ref "U2") (pin "25") (pinfunction "NC_6_25") (pintype "passive"))
      (node (ref "U2") (pin "29") (pinfunction "GND_A_29") (pintype "power_in"))
      (node (ref "U2") (pin "3") (pinfunction "NC_2_3") (pintype "passive"))
      (node (ref "U2") (pin "30") (pinfunction "GND_B_30") (pintype "power_in"))
      (node (ref "U2") (pin "34") (pinfunction "NC_7_34") (pintype "passive"))
      (node (ref "U2") (pin "35") (pinfunction "NC_8_35") (pintype "passive"))
      (node (ref "U2") (pin "36") (pinfunction "GND_3_36") (pintype "power_in"))
      (node (ref "U2") (pin "37") (pinfunction "GND_37") (pintype "power_in"))
      (node (ref "U2") (pin "38") (pinfunction "GND_C_38") (pintype "power_in"))
      (node (ref "U2") (pin "4") (pinfunction "NC_3_4") (pintype "passive"))
      (node (ref "U2") (pin "42") (pinfunction "NC_42") (pintype "passive"))
      (node (ref "U2") (pin "EPAD") (pinfunction "EPAD_EPAD") (pintype "passive"))
      (node (ref "U2") (pin "P$1") (pinfunction "EPAD_P$1") (pintype "passive"))
      (node (ref "U2") (pin "P$10") (pinfunction "EPAD_P$10") (pintype "passive"))
      (node (ref "U2") (pin "P$11") (pinfunction "EPAD_P$11") (pintype "passive"))
      (node (ref "U2") (pin "P$12") (pinfunction "EPAD_P$12") (pintype "passive"))
      (node (ref "U2") (pin "P$13") (pinfunction "EPAD_P$13") (pintype "passive"))
      (node (ref "U2") (pin "P$14") (pinfunction "EPAD_P$14") (pintype "passive"))
      (node (ref "U2") (pin "P$15") (pinfunction "EPAD_P$15") (pintype "passive"))
      (node (ref "U2") (pin "P$16") (pinfunction "EPAD_P$16") (pintype "passive"))
      (node (ref "U2") (pin "P$17") (pinfunction "EPAD_P$17") (pintype "passive"))
      (node (ref "U2") (pin "P$18") (pinfunction "EPAD_P$18") (pintype "passive"))
      (node (ref "U2") (pin "P$19") (pinfunction "EPAD_P$19") (pintype "passive"))
      (node (ref "U2") (pin "P$2") (pinfunction "EPAD_P$2") (pintype "passive"))
      (node (ref "U2") (pin "P$20") (pinfunction "EPAD_P$20") (pintype "passive"))
      (node (ref "U2") (pin "P$21") (pinfunction "EPAD_P$21") (pintype "passive"))
      (node (ref "U2") (pin "P$22") (pinfunction "EPAD_P$22") (pintype "passive"))
      (node (ref "U2") (pin "P$23") (pinfunction "EPAD_P$23") (pintype "passive"))
      (node (ref "U2") (pin "P$24") (pinfunction "EPAD_P$24") (pintype "passive"))
      (node (ref "U2") (pin "P$25") (pinfunction "EPAD_P$25") (pintype "passive"))
      (node (ref "U2") (pin "P$26") (pinfunction "EPAD_P$26") (pintype "passive"))
      (node (ref "U2") (pin "P$27") (pinfunction "EPAD_P$27") (pintype "passive"))
      (node (ref "U2") (pin "P$28") (pinfunction "EPAD_P$28") (pintype "passive"))
      (node (ref "U2") (pin "P$29") (pinfunction "EPAD_P$29") (pintype "passive"))
      (node (ref "U2") (pin "P$3") (pinfunction "EPAD_P$3") (pintype "passive"))
      (node (ref "U2") (pin "P$30") (pinfunction "EPAD_P$30") (pintype "passive"))
      (node (ref "U2") (pin "P$31") (pinfunction "EPAD_P$31") (pintype "passive"))
      (node (ref "U2") (pin "P$32") (pinfunction "EPAD_P$32") (pintype "passive"))
      (node (ref "U2") (pin "P$33") (pinfunction "EPAD_P$33") (pintype "passive"))
      (node (ref "U2") (pin "P$4") (pinfunction "EPAD_P$4") (pintype "passive"))
      (node (ref "U2") (pin "P$5") (pinfunction "EPAD_P$5") (pintype "passive"))
      (node (ref "U2") (pin "P$6") (pinfunction "EPAD_P$6") (pintype "passive"))
      (node (ref "U2") (pin "P$7") (pinfunction "EPAD_P$7") (pintype "passive"))
      (node (ref "U2") (pin "P$8") (pinfunction "EPAD_P$8") (pintype "passive"))
      (node (ref "U2") (pin "P$9") (pinfunction "EPAD_P$9") (pintype "passive"))
      (node (ref "U3") (pin "13") (pinfunction "GND_2_13") (pintype "power_in"))
      (node (ref "U3") (pin "19") (pinfunction "NC_4_19") (pintype "passive"))
      (node (ref "U3") (pin "20") (pinfunction "NC_5_20") (pintype "passive"))
      (node (ref "U3") (pin "25") (pinfunction "NC_6_25") (pintype "passive"))
      (node (ref "U3") (pin "29") (pinfunction "GND_A_29") (pintype "power_in"))
      (node (ref "U3") (pin "3") (pinfunction "NC_2_3") (pintype "passive"))
      (node (ref "U3") (pin "30") (pinfunction "GND_B_30") (pintype "power_in"))
      (node (ref "U3") (pin "34") (pinfunction "NC_7_34") (pintype "passive"))
      (node (ref "U3") (pin "35") (pinfunction "NC_8_35") (pintype "passive"))
      (node (ref "U3") (pin "36") (pinfunction "GND_3_36") (pintype "power_in"))
      (node (ref "U3") (pin "37") (pinfunction "GND_37") (pintype "power_in"))
      (node (ref "U3") (pin "38") (pinfunction "GND_C_38") (pintype "power_in"))
      (node (ref "U3") (pin "4") (pinfunction "NC_3_4") (pintype "passive"))
      (node (ref "U3") (pin "42") (pinfunction "NC_42") (pintype "passive"))
      (node (ref "U3") (pin "EPAD") (pinfunction "EPAD_EPAD") (pintype "passive"))
      (node (ref "U3") (pin "P$1") (pinfunction "EPAD_P$1") (pintype "passive"))
      (node (ref "U3") (pin "P$10") (pinfunction "EPAD_P$10") (pintype "passive"))
      (node (ref "U3") (pin "P$11") (pinfunction "EPAD_P$11") (pintype "passive"))
      (node (ref "U3") (pin "P$12") (pinfunction "EPAD_P$12") (pintype "passive"))
      (node (ref "U3") (pin "P$13") (pinfunction "EPAD_P$13") (pintype "passive"))
      (node (ref "U3") (pin "P$14") (pinfunction "EPAD_P$14") (pintype "passive"))
      (node (ref "U3") (pin "P$15") (pinfunction "EPAD_P$15") (pintype "passive"))
      (node (ref "U3") (pin "P$16") (pinfunction "EPAD_P$16") (pintype "passive"))
      (node (ref "U3") (pin "P$17") (pinfunction "EPAD_P$17") (pintype "passive"))
      (node (ref "U3") (pin "P$18") (pinfunction "EPAD_P$18") (pintype "passive"))
      (node (ref "U3") (pin "P$19") (pinfunction "EPAD_P$19") (pintype "passive"))
      (node (ref "U3") (pin "P$2") (pinfunction "EPAD_P$2") (pintype "passive"))
      (node (ref "U3") (pin "P$20") (pinfunction "EPAD_P$20") (pintype "passive"))
      (node (ref "U3") (pin "P$21") (pinfunction "EPAD_P$21") (pintype "passive"))
      (node (ref "U3") (pin "P$22") (pinfunction "EPAD_P$22") (pintype "passive"))
      (node (ref "U3") (pin "P$23") (pinfunction "EPAD_P$23") (pintype "passive"))
      (node (ref "U3") (pin "P$24") (pinfunction "EPAD_P$24") (pintype "passive"))
      (node (ref "U3") (pin "P$25") (pinfunction "EPAD_P$25") (pintype "passive"))
      (node (ref "U3") (pin "P$26") (pinfunction "EPAD_P$26") (pintype "passive"))
      (node (ref "U3") (pin "P$27") (pinfunction "EPAD_P$27") (pintype "passive"))
      (node (ref "U3") (pin "P$28") (pinfunction "EPAD_P$28") (pintype "passive"))
      (node (ref "U3") (pin "P$29") (pinfunction "EPAD_P$29") (pintype "passive"))
      (node (ref "U3") (pin "P$3") (pinfunction "EPAD_P$3") (pintype "passive"))
      (node (ref "U3") (pin "P$30") (pinfunction "EPAD_P$30") (pintype "passive"))
      (node (ref "U3") (pin "P$31") (pinfunction "EPAD_P$31") (pintype "passive"))
      (node (ref "U3") (pin "P$32") (pinfunction "EPAD_P$32") (pintype "passive"))
      (node (ref "U3") (pin "P$33") (pinfunction "EPAD_P$33") (pintype "passive"))
      (node (ref "U3") (pin "P$4") (pinfunction "EPAD_P$4") (pintype "passive"))
      (node (ref "U3") (pin "P$5") (pinfunction "EPAD_P$5") (pintype "passive"))
      (node (ref "U3") (pin "P$6") (pinfunction "EPAD_P$6") (pintype "passive"))
      (node (ref "U3") (pin "P$7") (pinfunction "EPAD_P$7") (pintype "passive"))
      (node (ref "U3") (pin "P$8") (pinfunction "EPAD_P$8") (pintype "passive"))
      (node (ref "U3") (pin "P$9") (pinfunction "EPAD_P$9") (pintype "passive"))
      (node (ref "U4") (pin "13") (pinfunction "VSS_2_13") (pintype "power_in"))
      (node (ref "U4") (pin "31") (pinfunction "AVSS_31") (pintype "power_in"))
      (node (ref "U4") (pin "36") (pinfunction "VSS_3_36") (pintype "power_in"))
      (node (ref "U4") (pin "45") (pinfunction "VSS_4_45") (pintype "power_in"))
      (node (ref "U4") (pin "53") (pinfunction "VSS_5_53") (pintype "power_in"))
      (node (ref "U4") (pin "63") (pinfunction "VSS_6_63") (pintype "power_in"))
      (node (ref "U4") (pin "75") (pinfunction "VSS_7_75") (pintype "power_in"))
      (node (ref "U4") (pin "84") (pinfunction "VSS_8_84") (pintype "power_in"))
      (node (ref "U4") (pin "92") (pinfunction "VSS_92") (pintype "power_in"))
    )
    (net (code "44") (name "/HALLA") (class "Default")
      (node (ref "MC") (pin "8") (pinfunction "8_8") (pintype "passive"))
      (node (ref "R4") (pin "2") (pinfunction "2_2") (pintype "passive"))
      (node (ref "U$1") (pin "7") (pinfunction "RP35_7") (pintype "bidirectional"))
    )
    (net (code "45") (name "/HALLA1") (class "Default")
      (node (ref "MC1") (pin "8") (pinfunction "8_8") (pintype "passive"))
      (node (ref "R18") (pin "2") (pinfunction "2_2") (pintype "passive"))
      (node (ref "U$2") (pin "7") (pinfunction "RP35_7") (pintype "bidirectional"))
    )
    (net (code "46") (name "/HALLA2") (class "Default")
      (node (ref "MC2") (pin "8") (pinfunction "8_8") (pintype "passive"))
      (node (ref "R32") (pin "2") (pinfunction "2_2") (pintype "passive"))
      (node (ref "U$3") (pin "7") (pinfunction "RP35_7") (pintype "bidirectional"))
    )
    (net (code "47") (name "/HALLB") (class "Default")
      (node (ref "MC") (pin "7") (pinfunction "7_7") (pintype "passive"))
      (node (ref "R5") (pin "2") (pinfunction "2_2") (pintype "passive"))
      (node (ref "U$1") (pin "11") (pinfunction "RP36_11") (pintype "bidirectional"))
    )
    (net (code "48") (name "/HALLB1") (class "Default")
      (node (ref "MC1") (pin "7") (pinfunction "7_7") (pintype "passive"))
      (node (ref "R19") (pin "2") (pinfunction "2_2") (pintype "passive"))
      (node (ref "U$2") (pin "11") (pinfunction "RP36_11") (pintype "bidirectional"))
    )
    (net (code "49") (name "/HALLB2") (class "Default")
      (node (ref "MC2") (pin "7") (pinfunction "7_7") (pintype "passive"))
      (node (ref "R33") (pin "2") (pinfunction "2_2") (pintype "passive"))
      (node (ref "U$3") (pin "11") (pinfunction "RP36_11") (pintype "bidirectional"))
    )
    (net (code "50") (name "/HALLC") (class "Default")
      (node (ref "MC") (pin "6") (pinfunction "6_6") (pintype "passive"))
      (node (ref "R6") (pin "2") (pinfunction "2_2") (pintype "passive"))
      (node (ref "U$1") (pin "12") (pinfunction "RP20_12") (pintype "bidirectional"))
    )
    (net (code "51") (name "/HALLC1") (class "Default")
      (node (ref "MC1") (pin "6") (pinfunction "6_6") (pintype "passive"))
      (node (ref "R20") (pin "2") (pinfunction "2_2") (pintype "passive"))
      (node (ref "U$2") (pin "12") (pinfunction "RP20_12") (pintype "bidirectional"))
    )
    (net (code "52") (name "/HALLC2") (class "Default")
      (node (ref "MC2") (pin "6") (pinfunction "6_6") (pintype "passive"))
      (node (ref "R34") (pin "2") (pinfunction "2_2") (pintype "passive"))
      (node (ref "U$3") (pin "12") (pinfunction "RP20_12") (pintype "bidirectional"))
    )
    (net (code "53") (name "/IMESA") (class "Default")
      (node (ref "CS1") (pin "7") (pinfunction "OUT2_7") (pintype "bidirectional"))
      (node (ref "U$1") (pin "5") (pinfunction "AN3/RPI33_5") (pintype "bidirectional"))
    )
    (net (code "54") (name "/IMESA1") (class "Default")
      (node (ref "CS2") (pin "7") (pinfunction "OUT2_7") (pintype "bidirectional"))
      (node (ref "U$2") (pin "5") (pinfunction "AN3/RPI33_5") (pintype "bidirectional"))
    )
    (net (code "55") (name "/IMESA2") (class "Default")
      (node (ref "CS3") (pin "7") (pinfunction "OUT2_7") (pintype "bidirectional"))
      (node (ref "U$3") (pin "5") (pinfunction "AN3/RPI33_5") (pintype "bidirectional"))
    )
    (net (code "56") (name "/IMESB") (class "Default")
      (node (ref "CS1") (pin "1") (pinfunction "OUT1_1") (pintype "bidirectional"))
      (node (ref "U$1") (pin "3") (pinfunction "AN1_3") (pintype "bidirectional"))
    )
    (net (code "57") (name "/IMESB1") (class "Default")
      (node (ref "CS2") (pin "1") (pinfunction "OUT1_1") (pintype "bidirectional"))
      (node (ref "U$2") (pin "3") (pinfunction "AN1_3") (pintype "bidirectional"))
    )
    (net (code "58") (name "/IMESB2") (class "Default")
      (node (ref "CS3") (pin "1") (pinfunction "OUT1_1") (pintype "bidirectional"))
      (node (ref "U$3") (pin "3") (pinfunction "AN1_3") (pintype "bidirectional"))
    )
    (net (code "59") (name "/LEDA") (class "Default")
      (node (ref "R9") (pin "1") (pinfunction "1_1") (pintype "passive"))
      (node (ref "U$1") (pin "6") (pinfunction "RPI34_6") (pintype "bidirectional"))
    )
    (net (code "60") (name "/LEDA1") (class "Default")
      (node (ref "R26") (pin "1") (pinfunction "1_1") (pintype "passive"))
      (node (ref "U$2") (pin "6") (pinfunction "RPI34_6") (pintype "bidirectional"))
    )
    (net (code "61") (name "/LEDA2") (class "Default")
      (node (ref "R40") (pin "1") (pinfunction "1_1") (pintype "passive"))
      (node (ref "U$3") (pin "6") (pinfunction "RPI34_6") (pintype "bidirectional"))
    )
    (net (code "62") (name "/LEDB") (class "Default")
      (node (ref "R13") (pin "1") (pinfunction "1_1") (pintype "passive"))
      (node (ref "U$1") (pin "9") (pinfunction "RA2_9") (pintype "bidirectional"))
    )
    (net (code "63") (name "/LEDB1") (class "Default")
      (node (ref "R27") (pin "1") (pinfunction "1_1") (pintype "passive"))
      (node (ref "U$2") (pin "9") (pinfunction "RA2_9") (pintype "bidirectional"))
    )
    (net (code "64") (name "/LEDB2") (class "Default")
      (node (ref "R41") (pin "1") (pinfunction "1_1") (pintype "passive"))
      (node (ref "U$3") (pin "9") (pinfunction "RA2_9") (pintype "bidirectional"))
    )
    (net (code "65") (name "/LEDC") (class "Default")
      (node (ref "R14") (pin "1") (pinfunction "1_1") (pintype "passive"))
      (node (ref "U$1") (pin "10") (pinfunction "RA3_10") (pintype "bidirectional"))
    )
    (net (code "66") (name "/LEDC1") (class "Default")
      (node (ref "R28") (pin "1") (pinfunction "1_1") (pintype "passive"))
      (node (ref "U$2") (pin "10") (pinfunction "RA3_10") (pintype "bidirectional"))
    )
    (net (code "67") (name "/LEDC2") (class "Default")
      (node (ref "R42") (pin "1") (pinfunction "1_1") (pintype "passive"))
      (node (ref "U$3") (pin "10") (pinfunction "RA3_10") (pintype "bidirectional"))
    )
    (net (code "68") (name "/MCLR") (class "Default")
      (node (ref "PICKIT") (pin "1") (pinfunction "1_1") (pintype "passive"))
      (node (ref "R1") (pin "1") (pinfunction "1_1") (pintype "passive"))
      (node (ref "U$1") (pin "1") (pinfunction "MCLR'_1") (pintype "bidirectional"))
    )
    (net (code "69") (name "/MCLR1") (class "Default")
      (node (ref "PICKIT1") (pin "1") (pinfunction "1_1") (pintype "passive"))
      (node (ref "R15") (pin "1") (pinfunction "1_1") (pintype "passive"))
      (node (ref "U$2") (pin "1") (pinfunction "MCLR'_1") (pintype "bidirectional"))
    )
    (net (code "70") (name "/MCLR2") (class "Default")
      (node (ref "PICKIT2") (pin "1") (pinfunction "1_1") (pintype "passive"))
      (node (ref "R29") (pin "1") (pinfunction "1_1") (pintype "passive"))
      (node (ref "U$3") (pin "1") (pinfunction "MCLR'_1") (pintype "bidirectional"))
    )
    (net (code "71") (name "/MCLR_BP") (class "Default")
      (node (ref "PICKIT3") (pin "1") (pinfunction "1_1") (pintype "passive"))
      (node (ref "R43") (pin "1") (pinfunction "1_1") (pintype "passive"))
      (node (ref "U4") (pin "15") (pinfunction "*MCLR_15") (pintype "passive"))
    )
    (net (code "72") (name "/MES_VBAT") (class "Default")
      (node (ref "R7") (pin "2") (pinfunction "2_2") (pintype "passive"))
      (node (ref "R8") (pin "1") (pinfunction "1_1") (pintype "passive"))
      (node (ref "U$1") (pin "2") (pinfunction "AN0_2") (pintype "bidirectional"))
    )
    (net (code "73") (name "/MES_VBAT1") (class "Default")
      (node (ref "R24") (pin "2") (pinfunction "2_2") (pintype "passive"))
      (node (ref "R25") (pin "1") (pinfunction "1_1") (pintype "passive"))
      (node (ref "U$2") (pin "2") (pinfunction "AN0_2") (pintype "bidirectional"))
    )
    (net (code "74") (name "/MES_VBAT2") (class "Default")
      (node (ref "R38") (pin "2") (pinfunction "2_2") (pintype "passive"))
      (node (ref "R39") (pin "1") (pinfunction "1_1") (pintype "passive"))
      (node (ref "U$3") (pin "2") (pinfunction "AN0_2") (pintype "bidirectional"))
    )
    (net (code "75") (name "/N$31") (class "Default")
      (node (ref "C69") (pin "1") (pinfunction "1_1") (pintype "passive"))
      (node (ref "U$5") (pin "15") (pinfunction "V3P3OUT_15") (pintype "bidirectional"))
    )
    (net (code "76") (name "/N$38") (class "Default")
      (node (ref "U4") (pin "20") (pinfunction "AN45/C1INA/RPB5/RB5_20") (pintype "bidirectional"))
    )
    (net (code "77") (name "/N$60") (class "Default")
      (node (ref "C64") (pin "1") (pinfunction "1_1") (pintype "passive"))
      (node (ref "U$4") (pin "15") (pinfunction "V3P3OUT_15") (pintype "bidirectional"))
    )
    (net (code "78") (name "/OUT_A") (class "Default")
      (node (ref "C17") (pin "1") (pinfunction "1_1") (pintype "passive"))
      (node (ref "CS1") (pin "5") (pinfunction "RS2+_5") (pintype "bidirectional"))
      (node (ref "RSENSE_A") (pin "2") (pinfunction "2_2") (pintype "passive"))
      (node (ref "U2") (pin "28") (pinfunction "OUT_A_28") (pintype "output"))
    )
    (net (code "79") (name "/OUT_A1") (class "Default")
      (node (ref "C33") (pin "1") (pinfunction "1_1") (pintype "passive"))
      (node (ref "CS2") (pin "5") (pinfunction "RS2+_5") (pintype "bidirectional"))
      (node (ref "RSENSE_A1") (pin "2") (pinfunction "2_2") (pintype "passive"))
      (node (ref "U1") (pin "28") (pinfunction "OUT_A_28") (pintype "output"))
    )
    (net (code "80") (name "/OUT_A2") (class "Default")
      (node (ref "C50") (pin "1") (pinfunction "1_1") (pintype "passive"))
      (node (ref "CS3") (pin "5") (pinfunction "RS2+_5") (pintype "bidirectional"))
      (node (ref "RSENSE_A2") (pin "2") (pinfunction "2_2") (pintype "passive"))
      (node (ref "U3") (pin "28") (pinfunction "OUT_A_28") (pintype "output"))
    )
    (net (code "81") (name "/OUT_B") (class "Default")
      (node (ref "C16") (pin "2") (pinfunction "2_2") (pintype "passive"))
      (node (ref "CS1") (pin "3") (pinfunction "RS1+_3") (pintype "bidirectional"))
      (node (ref "RSENSE_B") (pin "2") (pinfunction "2_2") (pintype "passive"))
      (node (ref "U2") (pin "31") (pinfunction "OUT_B_31") (pintype "output"))
    )
    (net (code "82") (name "/OUT_B1") (class "Default")
      (node (ref "C32") (pin "2") (pinfunction "2_2") (pintype "passive"))
      (node (ref "CS2") (pin "3") (pinfunction "RS1+_3") (pintype "bidirectional"))
      (node (ref "RSENSE_B1") (pin "2") (pinfunction "2_2") (pintype "passive"))
      (node (ref "U1") (pin "31") (pinfunction "OUT_B_31") (pintype "output"))
    )
    (net (code "83") (name "/OUT_B2") (class "Default")
      (node (ref "C49") (pin "2") (pinfunction "2_2") (pintype "passive"))
      (node (ref "CS3") (pin "3") (pinfunction "RS1+_3") (pintype "bidirectional"))
      (node (ref "RSENSE_B2") (pin "2") (pinfunction "2_2") (pintype "passive"))
      (node (ref "U3") (pin "31") (pinfunction "OUT_B_31") (pintype "output"))
    )
    (net (code "84") (name "/PGC") (class "Default")
      (node (ref "PICKIT") (pin "5") (pinfunction "5_5") (pintype "passive"))
      (node (ref "U$1") (pin "15") (pinfunction "RP38_15") (pintype "bidirectional"))
    )
    (net (code "85") (name "/PGC1") (class "Default")
      (node (ref "PICKIT1") (pin "5") (pinfunction "5_5") (pintype "passive"))
      (node (ref "U$2") (pin "15") (pinfunction "RP38_15") (pintype "bidirectional"))
    )
    (net (code "86") (name "/PGC2") (class "Default")
      (node (ref "PICKIT2") (pin "5") (pinfunction "5_5") (pintype "passive"))
      (node (ref "U$3") (pin "15") (pinfunction "RP38_15") (pintype "bidirectional"))
    )
    (net (code "87") (name "/PGC_BP") (class "Default")
      (node (ref "PICKIT3") (pin "5") (pinfunction "5_5") (pintype "passive"))
      (node (ref "U4") (pin "24") (pinfunction "PGEC1/AN1/RPB1/RB1_24") (pintype "bidirectional"))
    )
    (net (code "88") (name "/PGD") (class "Default")
      (node (ref "PICKIT") (pin "4") (pinfunction "4_4") (pintype "passive"))
      (node (ref "U$1") (pin "14") (pinfunction "RP37_14") (pintype "bidirectional"))
    )
    (net (code "89") (name "/PGD1") (class "Default")
      (node (ref "PICKIT1") (pin "4") (pinfunction "4_4") (pintype "passive"))
      (node (ref "U$2") (pin "14") (pinfunction "RP37_14") (pintype "bidirectional"))
    )
    (net (code "90") (name "/PGD2") (class "Default")
      (node (ref "PICKIT2") (pin "4") (pinfunction "4_4") (pintype "passive"))
      (node (ref "U$3") (pin "14") (pinfunction "RP37_14") (pintype "bidirectional"))
    )
    (net (code "91") (name "/PGD_BP") (class "Default")
      (node (ref "PICKIT3") (pin "4") (pinfunction "4_4") (pintype "passive"))
      (node (ref "U4") (pin "25") (pinfunction "PGED1/AN0/RPB0/RB0_25") (pintype "bidirectional"))
    )
    (net (code "92") (name "/PHASE_A") (class "Default")
      (node (ref "CS1") (pin "6") (pinfunction "RS2-_6") (pintype "bidirectional"))
      (node (ref "MC") (pin "3") (pinfunction "3_3") (pintype "passive"))
      (node (ref "RSENSE_A") (pin "1") (pinfunction "1_1") (pintype "passive"))
    )
    (net (code "93") (name "/PHASE_A1") (class "Default")
      (node (ref "CS2") (pin "6") (pinfunction "RS2-_6") (pintype "bidirectional"))
      (node (ref "MC1") (pin "3") (pinfunction "3_3") (pintype "passive"))
      (node (ref "RSENSE_A1") (pin "1") (pinfunction "1_1") (pintype "passive"))
    )
    (net (code "94") (name "/PHASE_A2") (class "Default")
      (node (ref "CS3") (pin "6") (pinfunction "RS2-_6") (pintype "bidirectional"))
      (node (ref "MC2") (pin "3") (pinfunction "3_3") (pintype "passive"))
      (node (ref "RSENSE_A2") (pin "1") (pinfunction "1_1") (pintype "passive"))
    )
    (net (code "95") (name "/PHASE_B") (class "Default")
      (node (ref "CS1") (pin "2") (pinfunction "RS1-_2") (pintype "bidirectional"))
      (node (ref "MC") (pin "2") (pinfunction "2_2") (pintype "passive"))
      (node (ref "RSENSE_B") (pin "1") (pinfunction "1_1") (pintype "passive"))
    )
    (net (code "96") (name "/PHASE_B1") (class "Default")
      (node (ref "CS2") (pin "2") (pinfunction "RS1-_2") (pintype "bidirectional"))
      (node (ref "MC1") (pin "2") (pinfunction "2_2") (pintype "passive"))
      (node (ref "RSENSE_B1") (pin "1") (pinfunction "1_1") (pintype "passive"))
    )
    (net (code "97") (name "/PHASE_B2") (class "Default")
      (node (ref "CS3") (pin "2") (pinfunction "RS1-_2") (pintype "bidirectional"))
      (node (ref "MC2") (pin "2") (pinfunction "2_2") (pintype "passive"))
      (node (ref "RSENSE_B2") (pin "1") (pinfunction "1_1") (pintype "passive"))
    )
    (net (code "98") (name "/PHASE_C") (class "Default")
      (node (ref "MC") (pin "1") (pinfunction "1_1") (pintype "passive"))
      (node (ref "RSENSE_C") (pin "1") (pinfunction "1_1") (pintype "passive"))
    )
    (net (code "99") (name "/PHASE_C1") (class "Default")
      (node (ref "MC1") (pin "1") (pinfunction "1_1") (pintype "passive"))
      (node (ref "RSENSE_C1") (pin "1") (pinfunction "1_1") (pintype "passive"))
    )
    (net (code "100") (name "/PHASE_C2") (class "Default")
      (node (ref "MC2") (pin "1") (pinfunction "1_1") (pintype "passive"))
      (node (ref "RSENSE_C2") (pin "1") (pinfunction "1_1") (pintype "passive"))
    )
    (net (code "101") (name "/PWM_A") (class "Default")
      (node (ref "U$1") (pin "21") (pinfunction "PWM3H_21") (pintype "bidirectional"))
      (node (ref "U2") (pin "17") (pinfunction "PWM_A_17") (pintype "input"))
    )
    (net (code "102") (name "/PWM_A1") (class "Default")
      (node (ref "U$2") (pin "21") (pinfunction "PWM3H_21") (pintype "bidirectional"))
      (node (ref "U1") (pin "17") (pinfunction "PWM_A_17") (pintype "input"))
    )
    (net (code "103") (name "/PWM_A2") (class "Default")
      (node (ref "U$3") (pin "21") (pinfunction "PWM3H_21") (pintype "bidirectional"))
      (node (ref "U3") (pin "17") (pinfunction "PWM_A_17") (pintype "input"))
    )
    (net (code "104") (name "/PWM_B") (class "Default")
      (node (ref "U$1") (pin "23") (pinfunction "PWM2H_23") (pintype "bidirectional"))
      (node (ref "U2") (pin "15") (pinfunction "PWM_B_15") (pintype "input"))
    )
    (net (code "105") (name "/PWM_B1") (class "Default")
      (node (ref "U$2") (pin "23") (pinfunction "PWM2H_23") (pintype "bidirectional"))
      (node (ref "U1") (pin "15") (pinfunction "PWM_B_15") (pintype "input"))
    )
    (net (code "106") (name "/PWM_B2") (class "Default")
      (node (ref "U$3") (pin "23") (pinfunction "PWM2H_23") (pintype "bidirectional"))
      (node (ref "U3") (pin "15") (pinfunction "PWM_B_15") (pintype "input"))
    )
    (net (code "107") (name "/PWM_C") (class "Default")
      (node (ref "U$1") (pin "25") (pinfunction "PWM1H_25") (pintype "bidirectional"))
      (node (ref "U2") (pin "5") (pinfunction "PWM_C_5") (pintype "input"))
    )
    (net (code "108") (name "/PWM_C1") (class "Default")
      (node (ref "U$2") (pin "25") (pinfunction "PWM1H_25") (pintype "bidirectional"))
      (node (ref "U1") (pin "5") (pinfunction "PWM_C_5") (pintype "input"))
    )
    (net (code "109") (name "/PWM_C2") (class "Default")
      (node (ref "U$3") (pin "25") (pinfunction "PWM1H_25") (pintype "bidirectional"))
      (node (ref "U3") (pin "5") (pinfunction "PWM_C_5") (pintype "input"))
    )
    (net (code "110") (name "/RESET_8844_1") (class "Default")
      (node (ref "U$4") (pin "16") (pinfunction "NRESET_16") (pintype "bidirectional"))
      (node (ref "U4") (pin "7") (pinfunction "EBIA12/AN21/RPC2/PMA12/RC2_7") (pintype "bidirectional"))
    )
    (net (code "111") (name "/RESET_8844_2") (class "Default")
      (node (ref "U$5") (pin "16") (pinfunction "NRESET_16") (pintype "bidirectional"))
      (node (ref "U4") (pin "23") (pinfunction "AN2/C2INB/RPB2/RB2_23") (pintype "bidirectional"))
    )
    (net (code "112") (name "/RESET_A") (class "Default")
      (node (ref "U$1") (pin "22") (pinfunction "PWM3L_22") (pintype "bidirectional"))
      (node (ref "U2") (pin "16") (pinfunction "*RESET_A_16") (pintype "input"))
    )
    (net (code "113") (name "/RESET_A1") (class "Default")
      (node (ref "U$2") (pin "22") (pinfunction "PWM3L_22") (pintype "bidirectional"))
      (node (ref "U1") (pin "16") (pinfunction "*RESET_A_16") (pintype "input"))
    )
    (net (code "114") (name "/RESET_A2") (class "Default")
      (node (ref "U$3") (pin "22") (pinfunction "PWM3L_22") (pintype "bidirectional"))
      (node (ref "U3") (pin "16") (pinfunction "*RESET_A_16") (pintype "input"))
    )
    (net (code "115") (name "/RESET_B") (class "Default")
      (node (ref "U$1") (pin "24") (pinfunction "PWM2L_24") (pintype "bidirectional"))
      (node (ref "U2") (pin "7") (pinfunction "*RESET_B_7") (pintype "input"))
    )
    (net (code "116") (name "/RESET_B1") (class "Default")
      (node (ref "U$2") (pin "24") (pinfunction "PWM2L_24") (pintype "bidirectional"))
      (node (ref "U1") (pin "7") (pinfunction "*RESET_B_7") (pintype "input"))
    )
    (net (code "117") (name "/RESET_B2") (class "Default")
      (node (ref "U$3") (pin "24") (pinfunction "PWM2L_24") (pintype "bidirectional"))
      (node (ref "U3") (pin "7") (pinfunction "*RESET_B_7") (pintype "input"))
    )
    (net (code "118") (name "/RESET_C") (class "Default")
      (node (ref "U$1") (pin "26") (pinfunction "PWM1L_26") (pintype "bidirectional"))
      (node (ref "U2") (pin "6") (pinfunction "*RESET_C_6") (pintype "input"))
    )
    (net (code "119") (name "/RESET_C1") (class "Default")
      (node (ref "U$2") (pin "26") (pinfunction "PWM1L_26") (pintype "bidirectional"))
      (node (ref "U1") (pin "6") (pinfunction "*RESET_C_6") (pintype "input"))
    )
    (net (code "120") (name "/RESET_C2") (class "Default")
      (node (ref "U$3") (pin "26") (pinfunction "PWM1L_26") (pintype "bidirectional"))
      (node (ref "U3") (pin "6") (pinfunction "*RESET_C_6") (pintype "input"))
    )
    (net (code "121") (name "/RPB6") (class "Default")
      (node (ref "J2") (pin "2") (pinfunction "2_2") (pintype "passive"))
      (node (ref "U4") (pin "26") (pinfunction "PGEC2/AN46/RPB6/RB6_26") (pintype "bidirectional"))
    )
    (net (code "122") (name "/RPB7") (class "Default")
      (node (ref "J2") (pin "3") (pinfunction "3_3") (pintype "passive"))
      (node (ref "U4") (pin "27") (pinfunction "PGED2/AN47/RPB7/RB7_27") (pintype "bidirectional"))
    )
    (net (code "123") (name "/RPB8") (class "Default")
      (node (ref "J2") (pin "5") (pinfunction "5_5") (pintype "passive"))
      (node (ref "U4") (pin "32") (pinfunction "EBIA10/AN48/RPB8/PMA10/RB8_32") (pintype "bidirectional"))
    )
    (net (code "124") (name "/RPB9") (class "Default")
      (node (ref "J2") (pin "6") (pinfunction "6_6") (pintype "passive"))
      (node (ref "U4") (pin "33") (pinfunction "EBIA7/AN49/RPB9/PMA7/RB9_33") (pintype "bidirectional"))
    )
    (net (code "125") (name "/RPB10") (class "Default")
      (node (ref "J2") (pin "7") (pinfunction "7_7") (pintype "passive"))
      (node (ref "U4") (pin "34") (pinfunction "EBIA13/CVREFOUT/AN5/RPB10/PMA13/RB10_34") (pintype "bidirectional"))
    )
    (net (code "126") (name "/RPB14") (class "Default")
      (node (ref "J2") (pin "13") (pinfunction "13_13") (pintype "passive"))
      (node (ref "U4") (pin "43") (pinfunction "EBIA1/AN9/ERXD2/AETXD3/RPB14/SCK3/PMA1/RB14_43") (pintype "bidirectional"))
    )
    (net (code "127") (name "/RPB15") (class "Default")
      (node (ref "J2") (pin "14") (pinfunction "14_14") (pintype "passive"))
      (node (ref "U4") (pin "44") (pinfunction "EBIA0/AN10/ERXD3/AETXD2/RPB15/OCFB/PMA0/RB15_44") (pintype "bidirectional"))
    )
    (net (code "128") (name "/RPD14") (class "Default")
      (node (ref "J2") (pin "16") (pinfunction "16_16") (pintype "passive"))
      (node (ref "U4") (pin "47") (pinfunction "AN32/AETXD0/RPD14/RD14_47") (pintype "bidirectional"))
    )
    (net (code "129") (name "/RPF12") (class "Default")
      (node (ref "J2") (pin "10") (pinfunction "10_10") (pintype "passive"))
      (node (ref "U4") (pin "40") (pinfunction "TDO/EBIA17/AN31/RPF12/RF12_40") (pintype "bidirectional"))
    )
    (net (code "130") (name "/RPF13") (class "Default")
      (node (ref "J2") (pin "9") (pinfunction "9_9") (pintype "passive"))
      (node (ref "U4") (pin "39") (pinfunction "TDI/EBIA18/AN30/RPF13/SCK5/RF13_39") (pintype "bidirectional"))
    )
    (net (code "131") (name "/SCK") (class "Default")
      (node (ref "U$1") (pin "16") (pinfunction "SCK1_16") (pintype "bidirectional"))
      (node (ref "U4") (pin "71") (pinfunction "EMDIO/AEMDIO/RPD0/RTCC/INT0/RD0_71") (pintype "bidirectional"))
    )
    (net (code "132") (name "/SCK1") (class "Default")
      (node (ref "U$2") (pin "16") (pinfunction "SCK1_16") (pintype "bidirectional"))
      (node (ref "U4") (pin "58") (pinfunction "EBIRDY2/RPF8/SCL3/RF8_58") (pintype "bidirectional"))
    )
    (net (code "133") (name "/SCK2") (class "Default")
      (node (ref "U$3") (pin "16") (pinfunction "SCK1_16") (pintype "bidirectional"))
      (node (ref "U4") (pin "81") (pinfunction "*SQICS0/RPD4/RD4_81") (pintype "bidirectional"))
    )
    (net (code "134") (name "/SDI") (class "Default")
      (node (ref "U$1") (pin "18") (pinfunction "SDI1_18") (pintype "bidirectional"))
      (node (ref "U4") (pin "69") (pinfunction "RPD10/SCK4/RD10_69") (pintype "bidirectional"))
    )
    (net (code "135") (name "/SDI1") (class "Default")
      (node (ref "U$2") (pin "18") (pinfunction "SDI1_18") (pintype "bidirectional"))
      (node (ref "U4") (pin "56") (pinfunction "USBID/RPF3/RF3_56") (pintype "bidirectional"))
    )
    (net (code "136") (name "/SDI2") (class "Default")
      (node (ref "U$3") (pin "18") (pinfunction "SDI1_18") (pintype "bidirectional"))
      (node (ref "U4") (pin "78") (pinfunction "EBID15/ETXCLK/RPD3/PMD15/RD3_78") (pintype "bidirectional"))
    )
    (net (code "137") (name "/SDO") (class "Default")
      (node (ref "U$1") (pin "17") (pinfunction "SDO1_17") (pintype "bidirectional"))
      (node (ref "U4") (pin "70") (pinfunction "EMDC/AEMDC/RPD11/RD11_70") (pintype "bidirectional"))
    )
    (net (code "138") (name "/SDO1") (class "Default")
      (node (ref "U$2") (pin "17") (pinfunction "SDO1_17") (pintype "bidirectional"))
      (node (ref "U4") (pin "57") (pinfunction "EBIRDY3/RPF2/SDA3/RF2_57") (pintype "bidirectional"))
    )
    (net (code "139") (name "/SDO2") (class "Default")
      (node (ref "U$3") (pin "17") (pinfunction "SDO1_17") (pintype "bidirectional"))
      (node (ref "U4") (pin "79") (pinfunction "EBID12/ETXD2/RPD12/PMD12/RD12_79") (pintype "bidirectional"))
    )
    (net (code "140") (name "/SLEEP_8844_1") (class "Default")
      (node (ref "U$4") (pin "17") (pinfunction "NSLEEP_17") (pintype "bidirectional"))
      (node (ref "U4") (pin "6") (pinfunction "EBIA6/AN22/RPC1/PMA6/RC1_6") (pintype "bidirectional"))
    )
    (net (code "141") (name "/SLEEP_8844_2") (class "Default")
      (node (ref "U$5") (pin "17") (pinfunction "NSLEEP_17") (pintype "bidirectional"))
      (node (ref "U4") (pin "22") (pinfunction "AN3/C2INA/RPB3/RB3_22") (pintype "bidirectional"))
    )
    (net (code "142") (name "/SS") (class "Default")
      (node (ref "U$1") (pin "4") (pinfunction "SS1'_4") (pintype "bidirectional"))
      (node (ref "U4") (pin "68") (pinfunction "EBIA15/RPD9/PMCS2/PMA15/RD9_68") (pintype "bidirectional"))
    )
    (net (code "143") (name "/SS1") (class "Default")
      (node (ref "U$2") (pin "4") (pinfunction "SS1'_4") (pintype "bidirectional"))
      (node (ref "U4") (pin "48") (pinfunction "AN33/AETXD1/RPD15/SCK6/RD15_48") (pintype "bidirectional"))
    )
    (net (code "144") (name "/SS2") (class "Default")
      (node (ref "U$3") (pin "4") (pinfunction "SS1'_4") (pintype "bidirectional"))
      (node (ref "U4") (pin "77") (pinfunction "EBID14/ETXEN/RPD2/PMD14/RD2_77") (pintype "bidirectional"))
    )
    (net (code "145") (name "/VBAT") (class "Default")
      (node (ref "C10") (pin "1") (pinfunction "+_1") (pintype "passive"))
      (node (ref "C12") (pin "1") (pinfunction "1_1") (pintype "passive"))
      (node (ref "C13") (pin "1") (pinfunction "1_1") (pintype "passive"))
      (node (ref "C14") (pin "1") (pinfunction "1_1") (pintype "passive"))
      (node (ref "C26") (pin "1") (pinfunction "+_1") (pintype "passive"))
      (node (ref "C28") (pin "1") (pinfunction "1_1") (pintype "passive"))
      (node (ref "C29") (pin "1") (pinfunction "1_1") (pintype "passive"))
      (node (ref "C30") (pin "1") (pinfunction "1_1") (pintype "passive"))
      (node (ref "C43") (pin "1") (pinfunction "+_1") (pintype "passive"))
      (node (ref "C45") (pin "1") (pinfunction "1_1") (pintype "passive"))
      (node (ref "C46") (pin "1") (pinfunction "1_1") (pintype "passive"))
      (node (ref "C47") (pin "1") (pinfunction "1_1") (pintype "passive"))
      (node (ref "C60") (pin "1") (pinfunction "1_1") (pintype "passive"))
      (node (ref "C61") (pin "1") (pinfunction "1_1") (pintype "passive"))
      (node (ref "C63") (pin "1") (pinfunction "1_1") (pintype "passive"))
      (node (ref "C65") (pin "1") (pinfunction "1_1") (pintype "passive"))
      (node (ref "C66") (pin "1") (pinfunction "1_1") (pintype "passive"))
      (node (ref "C68") (pin "1") (pinfunction "1_1") (pintype "passive"))
      (node (ref "J1") (pin "1") (pinfunction "2_1") (pintype "passive"))
      (node (ref "POWER") (pin "2") (pinfunction "2_2") (pintype "passive"))
      (node (ref "POWER2") (pin "2") (pinfunction "2_2") (pintype "passive"))
      (node (ref "R16") (pin "2") (pinfunction "2_2") (pintype "passive"))
      (node (ref "R2") (pin "2") (pinfunction "2_2") (pintype "passive"))
      (node (ref "R24") (pin "1") (pinfunction "1_1") (pintype "passive"))
      (node (ref "R30") (pin "2") (pinfunction "2_2") (pintype "passive"))
      (node (ref "R38") (pin "1") (pinfunction "1_1") (pintype "passive"))
      (node (ref "R44") (pin "1") (pinfunction "1_1") (pintype "passive"))
      (node (ref "R7") (pin "1") (pinfunction "1_1") (pintype "passive"))
      (node (ref "U$4") (pin "11") (pinfunction "VM1_11") (pintype "bidirectional"))
      (node (ref "U$4") (pin "4") (pinfunction "VM_4") (pintype "bidirectional"))
      (node (ref "U$5") (pin "11") (pinfunction "VM1_11") (pintype "bidirectional"))
      (node (ref "U$5") (pin "4") (pinfunction "VM_4") (pintype "bidirectional"))
      (node (ref "U1") (pin "26") (pinfunction "PVDD_A_2_26") (pintype "power_in"))
      (node (ref "U1") (pin "27") (pinfunction "PVDD_A_27") (pintype "power_in"))
      (node (ref "U1") (pin "32") (pinfunction "PVDD_B_32") (pintype "power_in"))
      (node (ref "U1") (pin "40") (pinfunction "PVDD_C_2_40") (pintype "power_in"))
      (node (ref "U1") (pin "41") (pinfunction "PVDD_C_41") (pintype "power_in"))
      (node (ref "U2") (pin "26") (pinfunction "PVDD_A_2_26") (pintype "power_in"))
      (node (ref "U2") (pin "27") (pinfunction "PVDD_A_27") (pintype "power_in"))
      (node (ref "U2") (pin "32") (pinfunction "PVDD_B_32") (pintype "power_in"))
      (node (ref "U2") (pin "40") (pinfunction "PVDD_C_2_40") (pintype "power_in"))
      (node (ref "U2") (pin "41") (pinfunction "PVDD_C_41") (pintype "power_in"))
      (node (ref "U3") (pin "26") (pinfunction "PVDD_A_2_26") (pintype "power_in"))
      (node (ref "U3") (pin "27") (pinfunction "PVDD_A_27") (pintype "power_in"))
      (node (ref "U3") (pin "32") (pinfunction "PVDD_B_32") (pintype "power_in"))
      (node (ref "U3") (pin "40") (pinfunction "PVDD_C_2_40") (pintype "power_in"))
      (node (ref "U3") (pin "41") (pinfunction "PVDD_C_41") (pintype "power_in"))
    )
    (net (code "146") (name "/VBUS") (class "Default")
      (node (ref "U4") (pin "51") (pinfunction "VBUS_51") (pintype "power_in"))
    )
    (net (code "147") (name "/VCAP") (class "Default")
      (node (ref "C3") (pin "1") (pinfunction "1_1") (pintype "passive"))
      (node (ref "U$1") (pin "20") (pinfunction "VCAP_20") (pintype "bidirectional"))
    )
    (net (code "148") (name "/VCAP1") (class "Default")
      (node (ref "C20") (pin "1") (pinfunction "1_1") (pintype "passive"))
      (node (ref "U$2") (pin "20") (pinfunction "VCAP_20") (pintype "bidirectional"))
    )
    (net (code "149") (name "/VCAP2") (class "Default")
      (node (ref "C37") (pin "1") (pinfunction "1_1") (pintype "passive"))
      (node (ref "U$3") (pin "20") (pinfunction "VCAP_20") (pintype "bidirectional"))
    )
    (net (code "150") (name "/VCP") (class "Default")
      (node (ref "C63") (pin "2") (pinfunction "2_2") (pintype "passive"))
      (node (ref "U$4") (pin "3") (pinfunction "VCP_3") (pintype "bidirectional"))
    )
    (net (code "151") (name "/VCP1") (class "Default")
      (node (ref "C68") (pin "2") (pinfunction "2_2") (pintype "passive"))
      (node (ref "U$5") (pin "3") (pinfunction "VCP_3") (pintype "bidirectional"))
    )
    (net (code "152") (name "/VREG") (class "Default")
      (node (ref "U2") (pin "10") (pinfunction "M3_10") (pintype "input"))
      (node (ref "U2") (pin "11") (pinfunction "VREG_11") (pintype "power_in"))
    )
    (net (code "153") (name "/VREG1") (class "Default")
      (node (ref "U1") (pin "10") (pinfunction "M3_10") (pintype "input"))
      (node (ref "U1") (pin "11") (pinfunction "VREG_11") (pintype "power_in"))
    )
    (net (code "154") (name "/VREG2") (class "Default")
      (node (ref "U3") (pin "10") (pinfunction "M3_10") (pintype "input"))
      (node (ref "U3") (pin "11") (pinfunction "VREG_11") (pintype "power_in"))
    )
    (net (code "155") (name "/VUSB3V3") (class "Default")
      (node (ref "U4") (pin "52") (pinfunction "VUSB3V3_52") (pintype "power_in"))
    )
    (net (code "156") (name "Net-(C11-Pad1)") (class "Default")
      (node (ref "C11") (pin "1") (pinfunction "1_1") (pintype "passive"))
      (node (ref "R2") (pin "1") (pinfunction "1_1") (pintype "passive"))
    )
    (net (code "157") (name "Net-(C27-Pad1)") (class "Default")
      (node (ref "C27") (pin "1") (pinfunction "1_1") (pintype "passive"))
      (node (ref "R16") (pin "1") (pinfunction "1_1") (pintype "passive"))
    )
    (net (code "158") (name "Net-(C44-Pad1)") (class "Default")
      (node (ref "C44") (pin "1") (pinfunction "1_1") (pintype "passive"))
      (node (ref "R30") (pin "1") (pinfunction "1_1") (pintype "passive"))
    )
    (net (code "159") (name "Net-(LED1-A)") (class "Default")
      (node (ref "LED1") (pin "1") (pinfunction "A_1") (pintype "passive"))
      (node (ref "R12") (pin "2") (pinfunction "2_2") (pintype "passive"))
    )
    (net (code "160") (name "Net-(LED1-C)") (class "Default")
      (node (ref "LED1") (pin "2") (pinfunction "C_2") (pintype "passive"))
      (node (ref "U2") (pin "18") (pinfunction "*FAULT_18") (pintype "output"))
    )
    (net (code "161") (name "Net-(LED2-A)") (class "Default")
      (node (ref "LED2") (pin "1") (pinfunction "A_1") (pintype "passive"))
      (node (ref "R11") (pin "2") (pinfunction "2_2") (pintype "passive"))
    )
    (net (code "162") (name "Net-(LED2-C)") (class "Default")
      (node (ref "LED2") (pin "2") (pinfunction "C_2") (pintype "passive"))
      (node (ref "U2") (pin "21") (pinfunction "*OTW_21") (pintype "output"))
    )
    (net (code "163") (name "Net-(LED3-A)") (class "Default")
      (node (ref "LED3") (pin "1") (pinfunction "A_1") (pintype "passive"))
      (node (ref "R9") (pin "2") (pinfunction "2_2") (pintype "passive"))
    )
    (net (code "164") (name "Net-(LED4-A)") (class "Default")
      (node (ref "LED4") (pin "1") (pinfunction "A_1") (pintype "passive"))
      (node (ref "R13") (pin "2") (pinfunction "2_2") (pintype "passive"))
    )
    (net (code "165") (name "Net-(LED5-A)") (class "Default")
      (node (ref "LED5") (pin "1") (pinfunction "A_1") (pintype "passive"))
      (node (ref "R14") (pin "2") (pinfunction "2_2") (pintype "passive"))
    )
    (net (code "166") (name "Net-(LED6-A)") (class "Default")
      (node (ref "LED6") (pin "1") (pinfunction "A_1") (pintype "passive"))
      (node (ref "R23") (pin "2") (pinfunction "2_2") (pintype "passive"))
    )
    (net (code "167") (name "Net-(LED6-C)") (class "Default")
      (node (ref "LED6") (pin "2") (pinfunction "C_2") (pintype "passive"))
      (node (ref "U1") (pin "18") (pinfunction "*FAULT_18") (pintype "output"))
    )
    (net (code "168") (name "Net-(LED7-A)") (class "Default")
      (node (ref "LED7") (pin "1") (pinfunction "A_1") (pintype "passive"))
      (node (ref "R22") (pin "2") (pinfunction "2_2") (pintype "passive"))
    )
    (net (code "169") (name "Net-(LED7-C)") (class "Default")
      (node (ref "LED7") (pin "2") (pinfunction "C_2") (pintype "passive"))
      (node (ref "U1") (pin "21") (pinfunction "*OTW_21") (pintype "output"))
    )
    (net (code "170") (name "Net-(LED8-A)") (class "Default")
      (node (ref "LED8") (pin "1") (pinfunction "A_1") (pintype "passive"))
      (node (ref "R26") (pin "2") (pinfunction "2_2") (pintype "passive"))
    )
    (net (code "171") (name "Net-(LED9-A)") (class "Default")
      (node (ref "LED9") (pin "1") (pinfunction "A_1") (pintype "passive"))
      (node (ref "R27") (pin "2") (pinfunction "2_2") (pintype "passive"))
    )
    (net (code "172") (name "Net-(LED10-A)") (class "Default")
      (node (ref "LED10") (pin "1") (pinfunction "A_1") (pintype "passive"))
      (node (ref "R28") (pin "2") (pinfunction "2_2") (pintype "passive"))
    )
    (net (code "173") (name "Net-(LED11-A)") (class "Default")
      (node (ref "LED11") (pin "1") (pinfunction "A_1") (pintype "passive"))
      (node (ref "R37") (pin "2") (pinfunction "2_2") (pintype "passive"))
    )
    (net (code "174") (name "Net-(LED11-C)") (class "Default")
      (node (ref "LED11") (pin "2") (pinfunction "C_2") (pintype "passive"))
      (node (ref "U3") (pin "18") (pinfunction "*FAULT_18") (pintype "output"))
    )
    (net (code "175") (name "Net-(LED12-A)") (class "Default")
      (node (ref "LED12") (pin "1") (pinfunction "A_1") (pintype "passive"))
      (node (ref "R36") (pin "2") (pinfunction "2_2") (pintype "passive"))
    )
    (net (code "176") (name "Net-(LED12-C)") (class "Default")
      (node (ref "LED12") (pin "2") (pinfunction "C_2") (pintype "passive"))
      (node (ref "U3") (pin "21") (pinfunction "*OTW_21") (pintype "output"))
    )
    (net (code "177") (name "Net-(LED13-A)") (class "Default")
      (node (ref "LED13") (pin "1") (pinfunction "A_1") (pintype "passive"))
      (node (ref "R40") (pin "2") (pinfunction "2_2") (pintype "passive"))
    )
    (net (code "178") (name "Net-(LED14-A)") (class "Default")
      (node (ref "LED14") (pin "1") (pinfunction "A_1") (pintype "passive"))
      (node (ref "R41") (pin "2") (pinfunction "2_2") (pintype "passive"))
    )
    (net (code "179") (name "Net-(LED15-A)") (class "Default")
      (node (ref "LED15") (pin "1") (pinfunction "A_1") (pintype "passive"))
      (node (ref "R42") (pin "2") (pinfunction "2_2") (pintype "passive"))
    )
    (net (code "180") (name "Net-(U1-BST_A)") (class "Default")
      (node (ref "C33") (pin "2") (pinfunction "2_2") (pintype "passive"))
      (node (ref "U1") (pin "24") (pinfunction "BST_A_24") (pintype "power_in"))
    )
    (net (code "181") (name "Net-(U1-BST_B)") (class "Default")
      (node (ref "C32") (pin "1") (pinfunction "1_1") (pintype "passive"))
      (node (ref "U1") (pin "33") (pinfunction "BST_B_33") (pintype "power_in"))
    )
    (net (code "182") (name "Net-(U1-BST_C)") (class "Default")
      (node (ref "C31") (pin "1") (pinfunction "1_1") (pintype "passive"))
      (node (ref "U1") (pin "43") (pinfunction "BST_C_43") (pintype "power_in"))
    )
    (net (code "183") (name "Net-(U1-OC_ADJ)") (class "Default")
      (node (ref "R21") (pin "1") (pinfunction "1_1") (pintype "passive"))
      (node (ref "U1") (pin "14") (pinfunction "OC_ADJ_14") (pintype "output"))
    )
    (net (code "184") (name "Net-(U1-OUT_C)") (class "Default")
      (node (ref "C31") (pin "2") (pinfunction "2_2") (pintype "passive"))
      (node (ref "RSENSE_C1") (pin "2") (pinfunction "2_2") (pintype "passive"))
      (node (ref "U1") (pin "39") (pinfunction "OUT_C_39") (pintype "output"))
    )
    (net (code "185") (name "Net-(U2-BST_A)") (class "Default")
      (node (ref "C17") (pin "2") (pinfunction "2_2") (pintype "passive"))
      (node (ref "U2") (pin "24") (pinfunction "BST_A_24") (pintype "power_in"))
    )
    (net (code "186") (name "Net-(U2-BST_B)") (class "Default")
      (node (ref "C16") (pin "1") (pinfunction "1_1") (pintype "passive"))
      (node (ref "U2") (pin "33") (pinfunction "BST_B_33") (pintype "power_in"))
    )
    (net (code "187") (name "Net-(U2-BST_C)") (class "Default")
      (node (ref "C15") (pin "1") (pinfunction "1_1") (pintype "passive"))
      (node (ref "U2") (pin "43") (pinfunction "BST_C_43") (pintype "power_in"))
    )
    (net (code "188") (name "Net-(U2-OC_ADJ)") (class "Default")
      (node (ref "R10") (pin "1") (pinfunction "1_1") (pintype "passive"))
      (node (ref "U2") (pin "14") (pinfunction "OC_ADJ_14") (pintype "output"))
    )
    (net (code "189") (name "Net-(U2-OUT_C)") (class "Default")
      (node (ref "C15") (pin "2") (pinfunction "2_2") (pintype "passive"))
      (node (ref "RSENSE_C") (pin "2") (pinfunction "2_2") (pintype "passive"))
      (node (ref "U2") (pin "39") (pinfunction "OUT_C_39") (pintype "output"))
    )
    (net (code "190") (name "Net-(U3-BST_A)") (class "Default")
      (node (ref "C50") (pin "2") (pinfunction "2_2") (pintype "passive"))
      (node (ref "U3") (pin "24") (pinfunction "BST_A_24") (pintype "power_in"))
    )
    (net (code "191") (name "Net-(U3-BST_B)") (class "Default")
      (node (ref "C49") (pin "1") (pinfunction "1_1") (pintype "passive"))
      (node (ref "U3") (pin "33") (pinfunction "BST_B_33") (pintype "power_in"))
    )
    (net (code "192") (name "Net-(U3-BST_C)") (class "Default")
      (node (ref "C48") (pin "1") (pinfunction "1_1") (pintype "passive"))
      (node (ref "U3") (pin "43") (pinfunction "BST_C_43") (pintype "power_in"))
    )
    (net (code "193") (name "Net-(U3-OC_ADJ)") (class "Default")
      (node (ref "R35") (pin "1") (pinfunction "1_1") (pintype "passive"))
      (node (ref "U3") (pin "14") (pinfunction "OC_ADJ_14") (pintype "output"))
    )
    (net (code "194") (name "Net-(U3-OUT_C)") (class "Default")
      (node (ref "C48") (pin "2") (pinfunction "2_2") (pintype "passive"))
      (node (ref "RSENSE_C2") (pin "2") (pinfunction "2_2") (pintype "passive"))
      (node (ref "U3") (pin "39") (pinfunction "OUT_C_39") (pintype "output"))
    )
    (net (code "195") (name "unconnected-(PICKIT-Pad6)") (class "Default")
      (node (ref "PICKIT") (pin "6") (pinfunction "6_6") (pintype "passive"))
    )
    (net (code "196") (name "unconnected-(PICKIT1-Pad6)") (class "Default")
      (node (ref "PICKIT1") (pin "6") (pinfunction "6_6") (pintype "passive"))
    )
    (net (code "197") (name "unconnected-(PICKIT2-Pad6)") (class "Default")
      (node (ref "PICKIT2") (pin "6") (pinfunction "6_6") (pintype "passive"))
    )
    (net (code "198") (name "unconnected-(PICKIT3-Pad6)") (class "Default")
      (node (ref "PICKIT3") (pin "6") (pinfunction "6_6") (pintype "passive"))
    )
    (net (code "199") (name "unconnected-(U$4-NC-Pad12)") (class "Default")
      (node (ref "U$4") (pin "12") (pinfunction "NC_12") (pintype "bidirectional"))
    )
    (net (code "200") (name "unconnected-(U$4-NC1-Pad13)") (class "Default")
      (node (ref "U$4") (pin "13") (pinfunction "NC1_13") (pintype "bidirectional"))
    )
    (net (code "201") (name "unconnected-(U$5-NC-Pad12)") (class "Default")
      (node (ref "U$5") (pin "12") (pinfunction "NC_12") (pintype "bidirectional"))
    )
    (net (code "202") (name "unconnected-(U$5-NC1-Pad13)") (class "Default")
      (node (ref "U$5") (pin "13") (pinfunction "NC1_13") (pintype "bidirectional"))
    )
    (net (code "203") (name "unconnected-(U4-*EBICS0{slash}SCL2{slash}RA2-Pad59)") (class "Default")
      (node (ref "U4") (pin "59") (pinfunction "*EBICS0/SCL2/RA2_59") (pintype "bidirectional"))
    )
    (net (code "204") (name "unconnected-(U4-*SQICS1{slash}RPD5{slash}RD5-Pad82)") (class "Default")
      (node (ref "U4") (pin "82") (pinfunction "*SQICS1/RPD5/RD5_82") (pintype "bidirectional"))
    )
    (net (code "205") (name "unconnected-(U4-AETXCLK{slash}RPA14{slash}SCL1{slash}RA14-Pad66)") (class "Default")
      (node (ref "U4") (pin "66") (pinfunction "AETXCLK/RPA14/SCL1/RA14_66") (pintype "bidirectional"))
    )
    (net (code "206") (name "unconnected-(U4-AETXEN{slash}RPA15{slash}SDA1{slash}RA15-Pad67)") (class "Default")
      (node (ref "U4") (pin "67") (pinfunction "AETXEN/RPA15/SDA1/RA15_67") (pintype "bidirectional"))
    )
    (net (code "207") (name "unconnected-(U4-AN23{slash}AERXERR{slash}RG15-Pad1)") (class "Default")
      (node (ref "U4") (pin "1") (pinfunction "AN23/AERXERR/RG15_1") (pintype "bidirectional"))
    )
    (net (code "208") (name "unconnected-(U4-D+-Pad55)") (class "Default")
      (node (ref "U4") (pin "55") (pinfunction "D+_55") (pintype "passive"))
    )
    (net (code "209") (name "unconnected-(U4-D--Pad54)") (class "Default")
      (node (ref "U4") (pin "54") (pinfunction "D-_54") (pintype "passive"))
    )
    (net (code "210") (name "unconnected-(U4-EBIA5{slash}AN34{slash}PMA5{slash}RA5-Pad2)") (class "Default")
      (node (ref "U4") (pin "2") (pinfunction "EBIA5/AN34/PMA5/RA5_2") (pintype "bidirectional"))
    )
    (net (code "211") (name "unconnected-(U4-EBIA8{slash}RPF5{slash}SCL5{slash}PMA8{slash}RF5-Pad65)") (class "Default")
      (node (ref "U4") (pin "65") (pinfunction "EBIA8/RPF5/SCL5/PMA8/RF5_65") (pintype "bidirectional"))
    )
    (net (code "212") (name "unconnected-(U4-EBIA9{slash}RPF4{slash}SDA5{slash}PMA9{slash}RF4-Pad64)") (class "Default")
      (node (ref "U4") (pin "64") (pinfunction "EBIA9/RPF4/SDA5/PMA9/RF4_64") (pintype "bidirectional"))
    )
    (net (code "213") (name "unconnected-(U4-EBIA14{slash}PMCS1{slash}PMA14{slash}RA4-Pad61)") (class "Default")
      (node (ref "U4") (pin "61") (pinfunction "EBIA14/PMCS1/PMA14/RA4_61") (pintype "bidirectional"))
    )
    (net (code "214") (name "unconnected-(U4-EBID0{slash}PMD0{slash}RE0-Pad91)") (class "Default")
      (node (ref "U4") (pin "91") (pinfunction "EBID0/PMD0/RE0_91") (pintype "bidirectional"))
    )
    (net (code "215") (name "unconnected-(U4-EBID1{slash}PMD1{slash}RE1-Pad94)") (class "Default")
      (node (ref "U4") (pin "94") (pinfunction "EBID1/PMD1/RE1_94") (pintype "bidirectional"))
    )
    (net (code "216") (name "unconnected-(U4-EBID2{slash}PMD2{slash}RE2-Pad98)") (class "Default")
      (node (ref "U4") (pin "98") (pinfunction "EBID2/PMD2/RE2_98") (pintype "bidirectional"))
    )
    (net (code "217") (name "unconnected-(U4-EBID13{slash}ETXD3{slash}PMD13{slash}RD13-Pad80)") (class "Default")
      (node (ref "U4") (pin "80") (pinfunction "EBID13/ETXD3/PMD13/RD13_80") (pintype "bidirectional"))
    )
    (net (code "218") (name "unconnected-(U4-EBIRDY1{slash}SDA2{slash}RA3-Pad60)") (class "Default")
      (node (ref "U4") (pin "60") (pinfunction "EBIRDY1/SDA2/RA3_60") (pintype "bidirectional"))
    )
    (net (code "219") (name "unconnected-(U4-OSCI{slash}CLKI{slash}RC12-Pad49)") (class "Default")
      (node (ref "U4") (pin "49") (pinfunction "OSCI/CLKI/RC12_49") (pintype "bidirectional"))
    )
    (net (code "220") (name "unconnected-(U4-OSCO{slash}CLKO{slash}RC15-Pad50)") (class "Default")
      (node (ref "U4") (pin "50") (pinfunction "OSCO/CLKO/RC15_50") (pintype "bidirectional"))
    )
    (net (code "221") (name "unconnected-(U4-RPD1{slash}SCK1{slash}RD1-Pad76)") (class "Default")
      (node (ref "U4") (pin "76") (pinfunction "RPD1/SCK1/RD1_76") (pintype "bidirectional"))
    )
    (net (code "222") (name "unconnected-(U4-SOSCI{slash}RPC13{slash}RC13-Pad72)") (class "Default")
      (node (ref "U4") (pin "72") (pinfunction "SOSCI/RPC13/RC13_72") (pintype "bidirectional"))
    )
    (net (code "223") (name "unconnected-(U4-SOSCO{slash}RPC14{slash}T1CK{slash}RC14-Pad73)") (class "Default")
      (node (ref "U4") (pin "73") (pinfunction "SOSCO/RPC14/T1CK/RC14_73") (pintype "bidirectional"))
    )
    (net (code "224") (name "unconnected-(U4-TCK{slash}EBIA19{slash}AN29{slash}RA1-Pad38)") (class "Default")
      (node (ref "U4") (pin "38") (pinfunction "TCK/EBIA19/AN29/RA1_38") (pintype "bidirectional"))
    )
    (net (code "225") (name "unconnected-(U4-TRCLK{slash}SQICLK{slash}RA6-Pad89)") (class "Default")
      (node (ref "U4") (pin "89") (pinfunction "TRCLK/SQICLK/RA6_89") (pintype "bidirectional"))
    )
    (net (code "226") (name "unconnected-(U4-TRD0{slash}SQID0{slash}RG13-Pad97)") (class "Default")
      (node (ref "U4") (pin "97") (pinfunction "TRD0/SQID0/RG13_97") (pintype "bidirectional"))
    )
    (net (code "227") (name "unconnected-(U4-TRD1{slash}SQID1{slash}RG12-Pad96)") (class "Default")
      (node (ref "U4") (pin "96") (pinfunction "TRD1/SQID1/RG12_96") (pintype "bidirectional"))
    )
    (net (code "228") (name "unconnected-(U4-TRD2{slash}SQID2{slash}RG14-Pad95)") (class "Default")
      (node (ref "U4") (pin "95") (pinfunction "TRD2/SQID2/RG14_95") (pintype "bidirectional"))
    )
    (net (code "229") (name "unconnected-(U4-TRD3{slash}SQID3{slash}RA7-Pad90)") (class "Default")
      (node (ref "U4") (pin "90") (pinfunction "TRD3/SQID3/RA7_90") (pintype "bidirectional"))
    )
  )
)
